# 2high.net
KiCad netlist of a schematic drawn in EAGLE
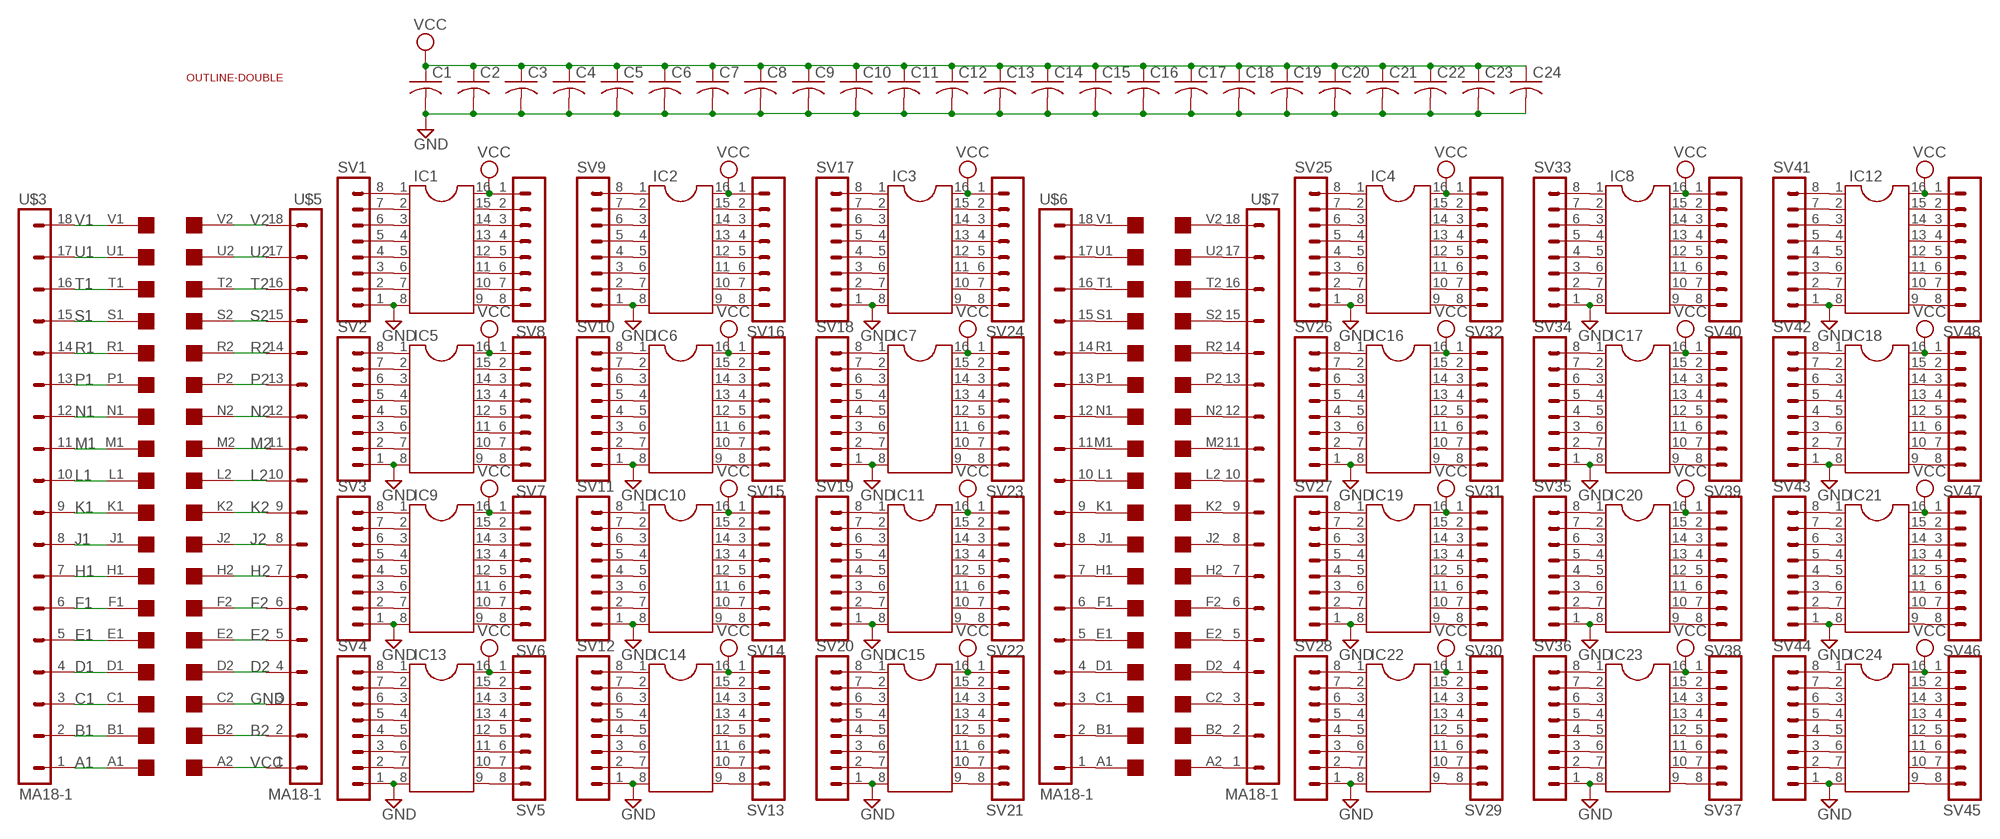
[diagram p0: schematic, sheet 1]

(export (version "E")
  (design (tool "Eeschema 10.0.6"))
  (components
    (comp (ref "C1")
      (value "C-US050-025X075")
      (footprint "eagle-import:C050-025X075")
      (libsource (lib "eagle-import") (part "C-US050-025X075"))
    )
    (comp (ref "C2")
      (value "C-US050-025X075")
      (footprint "eagle-import:C050-025X075")
      (libsource (lib "eagle-import") (part "C-US050-025X075"))
    )
    (comp (ref "C3")
      (value "C-US050-025X075")
      (footprint "eagle-import:C050-025X075")
      (libsource (lib "eagle-import") (part "C-US050-025X075"))
    )
    (comp (ref "C4")
      (value "C-US050-025X075")
      (footprint "eagle-import:C050-025X075")
      (libsource (lib "eagle-import") (part "C-US050-025X075"))
    )
    (comp (ref "C5")
      (value "C-US050-025X075")
      (footprint "eagle-import:C050-025X075")
      (libsource (lib "eagle-import") (part "C-US050-025X075"))
    )
    (comp (ref "C6")
      (value "C-US050-025X075")
      (footprint "eagle-import:C050-025X075")
      (libsource (lib "eagle-import") (part "C-US050-025X075"))
    )
    (comp (ref "C7")
      (value "C-US050-025X075")
      (footprint "eagle-import:C050-025X075")
      (libsource (lib "eagle-import") (part "C-US050-025X075"))
    )
    (comp (ref "C8")
      (value "C-US050-025X075")
      (footprint "eagle-import:C050-025X075")
      (libsource (lib "eagle-import") (part "C-US050-025X075"))
    )
    (comp (ref "C9")
      (value "C-US050-025X075")
      (footprint "eagle-import:C050-025X075")
      (libsource (lib "eagle-import") (part "C-US050-025X075"))
    )
    (comp (ref "C10")
      (value "C-US050-025X075")
      (footprint "eagle-import:C050-025X075")
      (libsource (lib "eagle-import") (part "C-US050-025X075"))
    )
    (comp (ref "C11")
      (value "C-US050-025X075")
      (footprint "eagle-import:C050-025X075")
      (libsource (lib "eagle-import") (part "C-US050-025X075"))
    )
    (comp (ref "C12")
      (value "C-US050-025X075")
      (footprint "eagle-import:C050-025X075")
      (libsource (lib "eagle-import") (part "C-US050-025X075"))
    )
    (comp (ref "C13")
      (value "C-US050-025X075")
      (footprint "eagle-import:C050-025X075")
      (libsource (lib "eagle-import") (part "C-US050-025X075"))
    )
    (comp (ref "C14")
      (value "C-US050-025X075")
      (footprint "eagle-import:C050-025X075")
      (libsource (lib "eagle-import") (part "C-US050-025X075"))
    )
    (comp (ref "C15")
      (value "C-US050-025X075")
      (footprint "eagle-import:C050-025X075")
      (libsource (lib "eagle-import") (part "C-US050-025X075"))
    )
    (comp (ref "C16")
      (value "C-US050-025X075")
      (footprint "eagle-import:C050-025X075")
      (libsource (lib "eagle-import") (part "C-US050-025X075"))
    )
    (comp (ref "C17")
      (value "C-US050-025X075")
      (footprint "eagle-import:C050-025X075")
      (libsource (lib "eagle-import") (part "C-US050-025X075"))
    )
    (comp (ref "C18")
      (value "C-US050-025X075")
      (footprint "eagle-import:C050-025X075")
      (libsource (lib "eagle-import") (part "C-US050-025X075"))
    )
    (comp (ref "C19")
      (value "C-US050-025X075")
      (footprint "eagle-import:C050-025X075")
      (libsource (lib "eagle-import") (part "C-US050-025X075"))
    )
    (comp (ref "C20")
      (value "C-US050-025X075")
      (footprint "eagle-import:C050-025X075")
      (libsource (lib "eagle-import") (part "C-US050-025X075"))
    )
    (comp (ref "C21")
      (value "C-US050-025X075")
      (footprint "eagle-import:C050-025X075")
      (libsource (lib "eagle-import") (part "C-US050-025X075"))
    )
    (comp (ref "C22")
      (value "C-US050-025X075")
      (footprint "eagle-import:C050-025X075")
      (libsource (lib "eagle-import") (part "C-US050-025X075"))
    )
    (comp (ref "C23")
      (value "C-US050-025X075")
      (footprint "eagle-import:C050-025X075")
      (libsource (lib "eagle-import") (part "C-US050-025X075"))
    )
    (comp (ref "C24")
      (value "C-US050-025X075")
      (footprint "eagle-import:C050-025X075")
      (libsource (lib "eagle-import") (part "C-US050-025X075"))
    )
    (comp (ref "IC1")
      (value "DIL16")
      (footprint "eagle-import:DIL16")
      (libsource (lib "eagle-import") (part "DIL16"))
    )
    (comp (ref "IC2")
      (value "DIL16")
      (footprint "eagle-import:DIL16")
      (libsource (lib "eagle-import") (part "DIL16"))
    )
    (comp (ref "IC3")
      (value "DIL16")
      (footprint "eagle-import:DIL16")
      (libsource (lib "eagle-import") (part "DIL16"))
    )
    (comp (ref "IC4")
      (value "DIL16")
      (footprint "eagle-import:DIL16")
      (libsource (lib "eagle-import") (part "DIL16"))
    )
    (comp (ref "IC5")
      (value "DIL16")
      (footprint "eagle-import:DIL16")
      (libsource (lib "eagle-import") (part "DIL16"))
    )
    (comp (ref "IC6")
      (value "DIL16")
      (footprint "eagle-import:DIL16")
      (libsource (lib "eagle-import") (part "DIL16"))
    )
    (comp (ref "IC7")
      (value "DIL16")
      (footprint "eagle-import:DIL16")
      (libsource (lib "eagle-import") (part "DIL16"))
    )
    (comp (ref "IC8")
      (value "DIL16")
      (footprint "eagle-import:DIL16")
      (libsource (lib "eagle-import") (part "DIL16"))
    )
    (comp (ref "IC9")
      (value "DIL16")
      (footprint "eagle-import:DIL16")
      (libsource (lib "eagle-import") (part "DIL16"))
    )
    (comp (ref "IC10")
      (value "DIL16")
      (footprint "eagle-import:DIL16")
      (libsource (lib "eagle-import") (part "DIL16"))
    )
    (comp (ref "IC11")
      (value "DIL16")
      (footprint "eagle-import:DIL16")
      (libsource (lib "eagle-import") (part "DIL16"))
    )
    (comp (ref "IC12")
      (value "DIL16")
      (footprint "eagle-import:DIL16")
      (libsource (lib "eagle-import") (part "DIL16"))
    )
    (comp (ref "IC13")
      (value "DIL16")
      (footprint "eagle-import:DIL16")
      (libsource (lib "eagle-import") (part "DIL16"))
    )
    (comp (ref "IC14")
      (value "DIL16")
      (footprint "eagle-import:DIL16")
      (libsource (lib "eagle-import") (part "DIL16"))
    )
    (comp (ref "IC15")
      (value "DIL16")
      (footprint "eagle-import:DIL16")
      (libsource (lib "eagle-import") (part "DIL16"))
    )
    (comp (ref "IC16")
      (value "DIL16")
      (footprint "eagle-import:DIL16")
      (libsource (lib "eagle-import") (part "DIL16"))
    )
    (comp (ref "IC17")
      (value "DIL16")
      (footprint "eagle-import:DIL16")
      (libsource (lib "eagle-import") (part "DIL16"))
    )
    (comp (ref "IC18")
      (value "DIL16")
      (footprint "eagle-import:DIL16")
      (libsource (lib "eagle-import") (part "DIL16"))
    )
    (comp (ref "IC19")
      (value "DIL16")
      (footprint "eagle-import:DIL16")
      (libsource (lib "eagle-import") (part "DIL16"))
    )
    (comp (ref "IC20")
      (value "DIL16")
      (footprint "eagle-import:DIL16")
      (libsource (lib "eagle-import") (part "DIL16"))
    )
    (comp (ref "IC21")
      (value "DIL16")
      (footprint "eagle-import:DIL16")
      (libsource (lib "eagle-import") (part "DIL16"))
    )
    (comp (ref "IC22")
      (value "DIL16")
      (footprint "eagle-import:DIL16")
      (libsource (lib "eagle-import") (part "DIL16"))
    )
    (comp (ref "IC23")
      (value "DIL16")
      (footprint "eagle-import:DIL16")
      (libsource (lib "eagle-import") (part "DIL16"))
    )
    (comp (ref "IC24")
      (value "DIL16")
      (footprint "eagle-import:DIL16")
      (libsource (lib "eagle-import") (part "DIL16"))
    )
    (comp (ref "SV1")
      (value "MA08-1")
      (footprint "eagle-import:MA08-1")
      (libsource (lib "eagle-import") (part "MA08-1"))
    )
    (comp (ref "SV2")
      (value "MA08-1")
      (footprint "eagle-import:MA08-1")
      (libsource (lib "eagle-import") (part "MA08-1"))
    )
    (comp (ref "SV3")
      (value "MA08-1")
      (footprint "eagle-import:MA08-1")
      (libsource (lib "eagle-import") (part "MA08-1"))
    )
    (comp (ref "SV4")
      (value "MA08-1")
      (footprint "eagle-import:MA08-1")
      (libsource (lib "eagle-import") (part "MA08-1"))
    )
    (comp (ref "SV5")
      (value "MA08-1")
      (footprint "eagle-import:MA08-1")
      (libsource (lib "eagle-import") (part "MA08-1"))
    )
    (comp (ref "SV6")
      (value "MA08-1")
      (footprint "eagle-import:MA08-1")
      (libsource (lib "eagle-import") (part "MA08-1"))
    )
    (comp (ref "SV7")
      (value "MA08-1")
      (footprint "eagle-import:MA08-1")
      (libsource (lib "eagle-import") (part "MA08-1"))
    )
    (comp (ref "SV8")
      (value "MA08-1")
      (footprint "eagle-import:MA08-1")
      (libsource (lib "eagle-import") (part "MA08-1"))
    )
    (comp (ref "SV9")
      (value "MA08-1")
      (footprint "eagle-import:MA08-1")
      (libsource (lib "eagle-import") (part "MA08-1"))
    )
    (comp (ref "SV10")
      (value "MA08-1")
      (footprint "eagle-import:MA08-1")
      (libsource (lib "eagle-import") (part "MA08-1"))
    )
    (comp (ref "SV11")
      (value "MA08-1")
      (footprint "eagle-import:MA08-1")
      (libsource (lib "eagle-import") (part "MA08-1"))
    )
    (comp (ref "SV12")
      (value "MA08-1")
      (footprint "eagle-import:MA08-1")
      (libsource (lib "eagle-import") (part "MA08-1"))
    )
    (comp (ref "SV13")
      (value "MA08-1")
      (footprint "eagle-import:MA08-1")
      (libsource (lib "eagle-import") (part "MA08-1"))
    )
    (comp (ref "SV14")
      (value "MA08-1")
      (footprint "eagle-import:MA08-1")
      (libsource (lib "eagle-import") (part "MA08-1"))
    )
    (comp (ref "SV15")
      (value "MA08-1")
      (footprint "eagle-import:MA08-1")
      (libsource (lib "eagle-import") (part "MA08-1"))
    )
    (comp (ref "SV16")
      (value "MA08-1")
      (footprint "eagle-import:MA08-1")
      (libsource (lib "eagle-import") (part "MA08-1"))
    )
    (comp (ref "SV17")
      (value "MA08-1")
      (footprint "eagle-import:MA08-1")
      (libsource (lib "eagle-import") (part "MA08-1"))
    )
    (comp (ref "SV18")
      (value "MA08-1")
      (footprint "eagle-import:MA08-1")
      (libsource (lib "eagle-import") (part "MA08-1"))
    )
    (comp (ref "SV19")
      (value "MA08-1")
      (footprint "eagle-import:MA08-1")
      (libsource (lib "eagle-import") (part "MA08-1"))
    )
    (comp (ref "SV20")
      (value "MA08-1")
      (footprint "eagle-import:MA08-1")
      (libsource (lib "eagle-import") (part "MA08-1"))
    )
    (comp (ref "SV21")
      (value "MA08-1")
      (footprint "eagle-import:MA08-1")
      (libsource (lib "eagle-import") (part "MA08-1"))
    )
    (comp (ref "SV22")
      (value "MA08-1")
      (footprint "eagle-import:MA08-1")
      (libsource (lib "eagle-import") (part "MA08-1"))
    )
    (comp (ref "SV23")
      (value "MA08-1")
      (footprint "eagle-import:MA08-1")
      (libsource (lib "eagle-import") (part "MA08-1"))
    )
    (comp (ref "SV24")
      (value "MA08-1")
      (footprint "eagle-import:MA08-1")
      (libsource (lib "eagle-import") (part "MA08-1"))
    )
    (comp (ref "SV25")
      (value "MA08-1")
      (footprint "eagle-import:MA08-1")
      (libsource (lib "eagle-import") (part "MA08-1"))
    )
    (comp (ref "SV26")
      (value "MA08-1")
      (footprint "eagle-import:MA08-1")
      (libsource (lib "eagle-import") (part "MA08-1"))
    )
    (comp (ref "SV27")
      (value "MA08-1")
      (footprint "eagle-import:MA08-1")
      (libsource (lib "eagle-import") (part "MA08-1"))
    )
    (comp (ref "SV28")
      (value "MA08-1")
      (footprint "eagle-import:MA08-1")
      (libsource (lib "eagle-import") (part "MA08-1"))
    )
    (comp (ref "SV29")
      (value "MA08-1")
      (footprint "eagle-import:MA08-1")
      (libsource (lib "eagle-import") (part "MA08-1"))
    )
    (comp (ref "SV30")
      (value "MA08-1")
      (footprint "eagle-import:MA08-1")
      (libsource (lib "eagle-import") (part "MA08-1"))
    )
    (comp (ref "SV31")
      (value "MA08-1")
      (footprint "eagle-import:MA08-1")
      (libsource (lib "eagle-import") (part "MA08-1"))
    )
    (comp (ref "SV32")
      (value "MA08-1")
      (footprint "eagle-import:MA08-1")
      (libsource (lib "eagle-import") (part "MA08-1"))
    )
    (comp (ref "SV33")
      (value "MA08-1")
      (footprint "eagle-import:MA08-1")
      (libsource (lib "eagle-import") (part "MA08-1"))
    )
    (comp (ref "SV34")
      (value "MA08-1")
      (footprint "eagle-import:MA08-1")
      (libsource (lib "eagle-import") (part "MA08-1"))
    )
    (comp (ref "SV35")
      (value "MA08-1")
      (footprint "eagle-import:MA08-1")
      (libsource (lib "eagle-import") (part "MA08-1"))
    )
    (comp (ref "SV36")
      (value "MA08-1")
      (footprint "eagle-import:MA08-1")
      (libsource (lib "eagle-import") (part "MA08-1"))
    )
    (comp (ref "SV37")
      (value "MA08-1")
      (footprint "eagle-import:MA08-1")
      (libsource (lib "eagle-import") (part "MA08-1"))
    )
    (comp (ref "SV38")
      (value "MA08-1")
      (footprint "eagle-import:MA08-1")
      (libsource (lib "eagle-import") (part "MA08-1"))
    )
    (comp (ref "SV39")
      (value "MA08-1")
      (footprint "eagle-import:MA08-1")
      (libsource (lib "eagle-import") (part "MA08-1"))
    )
    (comp (ref "SV40")
      (value "MA08-1")
      (footprint "eagle-import:MA08-1")
      (libsource (lib "eagle-import") (part "MA08-1"))
    )
    (comp (ref "SV41")
      (value "MA08-1")
      (footprint "eagle-import:MA08-1")
      (libsource (lib "eagle-import") (part "MA08-1"))
    )
    (comp (ref "SV42")
      (value "MA08-1")
      (footprint "eagle-import:MA08-1")
      (libsource (lib "eagle-import") (part "MA08-1"))
    )
    (comp (ref "SV43")
      (value "MA08-1")
      (footprint "eagle-import:MA08-1")
      (libsource (lib "eagle-import") (part "MA08-1"))
    )
    (comp (ref "SV44")
      (value "MA08-1")
      (footprint "eagle-import:MA08-1")
      (libsource (lib "eagle-import") (part "MA08-1"))
    )
    (comp (ref "SV45")
      (value "MA08-1")
      (footprint "eagle-import:MA08-1")
      (libsource (lib "eagle-import") (part "MA08-1"))
    )
    (comp (ref "SV46")
      (value "MA08-1")
      (footprint "eagle-import:MA08-1")
      (libsource (lib "eagle-import") (part "MA08-1"))
    )
    (comp (ref "SV47")
      (value "MA08-1")
      (footprint "eagle-import:MA08-1")
      (libsource (lib "eagle-import") (part "MA08-1"))
    )
    (comp (ref "SV48")
      (value "MA08-1")
      (footprint "eagle-import:MA08-1")
      (libsource (lib "eagle-import") (part "MA08-1"))
    )
    (comp (ref "U$1")
      (value "OUTLINE-DOUBLE")
      (footprint "eagle-import:DOUBLE")
      (libsource (lib "eagle-import") (part "OUTLINE-DOUBLE"))
    )
    (comp (ref "U$2")
      (value "EDGE-2CONNECTOR")
      (footprint "eagle-import:EDGE-CON2")
      (libsource (lib "eagle-import") (part "EDGE-2CONNECTOR"))
    )
    (comp (ref "U$3")
      (value "MA18-1")
      (footprint "eagle-import:MA18-1")
      (libsource (lib "eagle-import") (part "MA18-1"))
    )
    (comp (ref "U$4")
      (value "EDGE-2CONNECTOR")
      (footprint "eagle-import:EDGE-CON2")
      (libsource (lib "eagle-import") (part "EDGE-2CONNECTOR"))
    )
    (comp (ref "U$5")
      (value "MA18-1")
      (footprint "eagle-import:MA18-1")
      (libsource (lib "eagle-import") (part "MA18-1"))
    )
    (comp (ref "U$6")
      (value "MA18-1")
      (footprint "eagle-import:MA18-1")
      (libsource (lib "eagle-import") (part "MA18-1"))
    )
    (comp (ref "U$7")
      (value "MA18-1")
      (footprint "eagle-import:MA18-1")
      (libsource (lib "eagle-import") (part "MA18-1"))
    )
  )
  (nets
    (net (code "1") (name "/A1") (class "Default")
      (node (ref "U$3") (pin "1") (pinfunction "1_1") (pintype "passive"))
      (node (ref "U$4") (pin "A1") (pinfunction "1_A1") (pintype "bidirectional"))
    )
    (net (code "2") (name "/B1") (class "Default")
      (node (ref "U$3") (pin "2") (pinfunction "2_2") (pintype "passive"))
      (node (ref "U$4") (pin "B1") (pinfunction "1_B1") (pintype "bidirectional"))
    )
    (net (code "3") (name "/B2") (class "Default")
      (node (ref "U$4") (pin "B2") (pinfunction "1_B2") (pintype "bidirectional"))
      (node (ref "U$5") (pin "2") (pinfunction "2_2") (pintype "passive"))
    )
    (net (code "4") (name "/C1") (class "Default")
      (node (ref "U$3") (pin "3") (pinfunction "3_3") (pintype "passive"))
      (node (ref "U$4") (pin "C1") (pinfunction "1_C1") (pintype "bidirectional"))
    )
    (net (code "5") (name "/D1") (class "Default")
      (node (ref "U$3") (pin "4") (pinfunction "4_4") (pintype "passive"))
      (node (ref "U$4") (pin "D1") (pinfunction "1_D1") (pintype "bidirectional"))
    )
    (net (code "6") (name "/D2") (class "Default")
      (node (ref "U$4") (pin "D2") (pinfunction "1_D2") (pintype "bidirectional"))
      (node (ref "U$5") (pin "4") (pinfunction "4_4") (pintype "passive"))
    )
    (net (code "7") (name "/E1") (class "Default")
      (node (ref "U$3") (pin "5") (pinfunction "5_5") (pintype "passive"))
      (node (ref "U$4") (pin "E1") (pinfunction "1_E1") (pintype "bidirectional"))
    )
    (net (code "8") (name "/E2") (class "Default")
      (node (ref "U$4") (pin "E2") (pinfunction "1_E2") (pintype "bidirectional"))
      (node (ref "U$5") (pin "5") (pinfunction "5_5") (pintype "passive"))
    )
    (net (code "9") (name "/F1") (class "Default")
      (node (ref "U$3") (pin "6") (pinfunction "6_6") (pintype "passive"))
      (node (ref "U$4") (pin "F1") (pinfunction "1_F1") (pintype "bidirectional"))
    )
    (net (code "10") (name "/F2") (class "Default")
      (node (ref "U$4") (pin "F2") (pinfunction "1_F2") (pintype "bidirectional"))
      (node (ref "U$5") (pin "6") (pinfunction "6_6") (pintype "passive"))
    )
    (net (code "11") (name "/H1") (class "Default")
      (node (ref "U$3") (pin "7") (pinfunction "7_7") (pintype "passive"))
      (node (ref "U$4") (pin "H1") (pinfunction "1_H1") (pintype "bidirectional"))
    )
    (net (code "12") (name "/H2") (class "Default")
      (node (ref "U$4") (pin "H2") (pinfunction "1_H2") (pintype "bidirectional"))
      (node (ref "U$5") (pin "7") (pinfunction "7_7") (pintype "passive"))
    )
    (net (code "13") (name "/J1") (class "Default")
      (node (ref "U$3") (pin "8") (pinfunction "8_8") (pintype "passive"))
      (node (ref "U$4") (pin "J1") (pinfunction "1_J1") (pintype "bidirectional"))
    )
    (net (code "14") (name "/J2") (class "Default")
      (node (ref "U$4") (pin "J2") (pinfunction "1_J2") (pintype "bidirectional"))
      (node (ref "U$5") (pin "8") (pinfunction "8_8") (pintype "passive"))
    )
    (net (code "15") (name "/K1") (class "Default")
      (node (ref "U$3") (pin "9") (pinfunction "9_9") (pintype "passive"))
      (node (ref "U$4") (pin "K1") (pinfunction "1_K1") (pintype "bidirectional"))
    )
    (net (code "16") (name "/K2") (class "Default")
      (node (ref "U$4") (pin "K2") (pinfunction "1_K2") (pintype "bidirectional"))
      (node (ref "U$5") (pin "9") (pinfunction "9_9") (pintype "passive"))
    )
    (net (code "17") (name "/L1") (class "Default")
      (node (ref "U$3") (pin "10") (pinfunction "10_10") (pintype "passive"))
      (node (ref "U$4") (pin "L1") (pinfunction "1_L1") (pintype "bidirectional"))
    )
    (net (code "18") (name "/L2") (class "Default")
      (node (ref "U$4") (pin "L2") (pinfunction "1_L2") (pintype "bidirectional"))
      (node (ref "U$5") (pin "10") (pinfunction "10_10") (pintype "passive"))
    )
    (net (code "19") (name "/M1") (class "Default")
      (node (ref "U$3") (pin "11") (pinfunction "11_11") (pintype "passive"))
      (node (ref "U$4") (pin "M1") (pinfunction "1_M1") (pintype "bidirectional"))
    )
    (net (code "20") (name "/M2") (class "Default")
      (node (ref "U$4") (pin "M2") (pinfunction "1_M2") (pintype "bidirectional"))
      (node (ref "U$5") (pin "11") (pinfunction "11_11") (pintype "passive"))
    )
    (net (code "21") (name "/N1") (class "Default")
      (node (ref "U$3") (pin "12") (pinfunction "12_12") (pintype "passive"))
      (node (ref "U$4") (pin "N1") (pinfunction "1_N1") (pintype "bidirectional"))
    )
    (net (code "22") (name "/N2") (class "Default")
      (node (ref "U$4") (pin "N2") (pinfunction "1_N2") (pintype "bidirectional"))
      (node (ref "U$5") (pin "12") (pinfunction "12_12") (pintype "passive"))
    )
    (net (code "23") (name "/P1") (class "Default")
      (node (ref "U$3") (pin "13") (pinfunction "13_13") (pintype "passive"))
      (node (ref "U$4") (pin "P1") (pinfunction "1_P1") (pintype "bidirectional"))
    )
    (net (code "24") (name "/P2") (class "Default")
      (node (ref "U$4") (pin "P2") (pinfunction "1_P2") (pintype "bidirectional"))
      (node (ref "U$5") (pin "13") (pinfunction "13_13") (pintype "passive"))
    )
    (net (code "25") (name "/R1") (class "Default")
      (node (ref "U$3") (pin "14") (pinfunction "14_14") (pintype "passive"))
      (node (ref "U$4") (pin "R1") (pinfunction "1_R1") (pintype "bidirectional"))
    )
    (net (code "26") (name "/R2") (class "Default")
      (node (ref "U$4") (pin "R2") (pinfunction "1_R2") (pintype "bidirectional"))
      (node (ref "U$5") (pin "14") (pinfunction "14_14") (pintype "passive"))
    )
    (net (code "27") (name "/S1") (class "Default")
      (node (ref "U$3") (pin "15") (pinfunction "15_15") (pintype "passive"))
      (node (ref "U$4") (pin "S1") (pinfunction "1_S1") (pintype "bidirectional"))
    )
    (net (code "28") (name "/S2") (class "Default")
      (node (ref "U$4") (pin "S2") (pinfunction "1_S2") (pintype "bidirectional"))
      (node (ref "U$5") (pin "15") (pinfunction "15_15") (pintype "passive"))
    )
    (net (code "29") (name "/T1") (class "Default")
      (node (ref "U$3") (pin "16") (pinfunction "16_16") (pintype "passive"))
      (node (ref "U$4") (pin "T1") (pinfunction "1_T1") (pintype "bidirectional"))
    )
    (net (code "30") (name "/T2") (class "Default")
      (node (ref "U$4") (pin "T2") (pinfunction "1_T2") (pintype "bidirectional"))
      (node (ref "U$5") (pin "16") (pinfunction "16_16") (pintype "passive"))
    )
    (net (code "31") (name "/U1") (class "Default")
      (node (ref "U$3") (pin "17") (pinfunction "17_17") (pintype "passive"))
      (node (ref "U$4") (pin "U1") (pinfunction "1_U1") (pintype "bidirectional"))
    )
    (net (code "32") (name "/U2") (class "Default")
      (node (ref "U$4") (pin "U2") (pinfunction "1_U2") (pintype "bidirectional"))
      (node (ref "U$5") (pin "17") (pinfunction "17_17") (pintype "passive"))
    )
    (net (code "33") (name "/V1") (class "Default")
      (node (ref "U$3") (pin "18") (pinfunction "18_18") (pintype "passive"))
      (node (ref "U$4") (pin "V1") (pinfunction "1_V1") (pintype "bidirectional"))
    )
    (net (code "34") (name "/V2") (class "Default")
      (node (ref "U$4") (pin "V2") (pinfunction "1_V2") (pintype "bidirectional"))
      (node (ref "U$5") (pin "18") (pinfunction "18_18") (pintype "passive"))
    )
    (net (code "35") (name "GND") (class "Default")
      (node (ref "C1") (pin "2") (pinfunction "2_2") (pintype "passive"))
      (node (ref "C10") (pin "2") (pinfunction "2_2") (pintype "passive"))
      (node (ref "C11") (pin "2") (pinfunction "2_2") (pintype "passive"))
      (node (ref "C12") (pin "2") (pinfunction "2_2") (pintype "passive"))
      (node (ref "C13") (pin "2") (pinfunction "2_2") (pintype "passive"))
      (node (ref "C14") (pin "2") (pinfunction "2_2") (pintype "passive"))
      (node (ref "C15") (pin "2") (pinfunction "2_2") (pintype "passive"))
      (node (ref "C16") (pin "2") (pinfunction "2_2") (pintype "passive"))
      (node (ref "C17") (pin "2") (pinfunction "2_2") (pintype "passive"))
      (node (ref "C18") (pin "2") (pinfunction "2_2") (pintype "passive"))
      (node (ref "C19") (pin "2") (pinfunction "2_2") (pintype "passive"))
      (node (ref "C2") (pin "2") (pinfunction "2_2") (pintype "passive"))
      (node (ref "C20") (pin "2") (pinfunction "2_2") (pintype "passive"))
      (node (ref "C21") (pin "2") (pinfunction "2_2") (pintype "passive"))
      (node (ref "C22") (pin "2") (pinfunction "2_2") (pintype "passive"))
      (node (ref "C23") (pin "2") (pinfunction "2_2") (pintype "passive"))
      (node (ref "C24") (pin "2") (pinfunction "2_2") (pintype "passive"))
      (node (ref "C3") (pin "2") (pinfunction "2_2") (pintype "passive"))
      (node (ref "C4") (pin "2") (pinfunction "2_2") (pintype "passive"))
      (node (ref "C5") (pin "2") (pinfunction "2_2") (pintype "passive"))
      (node (ref "C6") (pin "2") (pinfunction "2_2") (pintype "passive"))
      (node (ref "C7") (pin "2") (pinfunction "2_2") (pintype "passive"))
      (node (ref "C8") (pin "2") (pinfunction "2_2") (pintype "passive"))
      (node (ref "C9") (pin "2") (pinfunction "2_2") (pintype "passive"))
      (node (ref "IC1") (pin "8") (pinfunction "8_8") (pintype "passive"))
      (node (ref "IC10") (pin "8") (pinfunction "8_8") (pintype "passive"))
      (node (ref "IC11") (pin "8") (pinfunction "8_8") (pintype "passive"))
      (node (ref "IC12") (pin "8") (pinfunction "8_8") (pintype "passive"))
      (node (ref "IC13") (pin "8") (pinfunction "8_8") (pintype "passive"))
      (node (ref "IC14") (pin "8") (pinfunction "8_8") (pintype "passive"))
      (node (ref "IC15") (pin "8") (pinfunction "8_8") (pintype "passive"))
      (node (ref "IC16") (pin "8") (pinfunction "8_8") (pintype "passive"))
      (node (ref "IC17") (pin "8") (pinfunction "8_8") (pintype "passive"))
      (node (ref "IC18") (pin "8") (pinfunction "8_8") (pintype "passive"))
      (node (ref "IC19") (pin "8") (pinfunction "8_8") (pintype "passive"))
      (node (ref "IC2") (pin "8") (pinfunction "8_8") (pintype "passive"))
      (node (ref "IC20") (pin "8") (pinfunction "8_8") (pintype "passive"))
      (node (ref "IC21") (pin "8") (pinfunction "8_8") (pintype "passive"))
      (node (ref "IC22") (pin "8") (pinfunction "8_8") (pintype "passive"))
      (node (ref "IC23") (pin "8") (pinfunction "8_8") (pintype "passive"))
      (node (ref "IC24") (pin "8") (pinfunction "8_8") (pintype "passive"))
      (node (ref "IC3") (pin "8") (pinfunction "8_8") (pintype "passive"))
      (node (ref "IC4") (pin "8") (pinfunction "8_8") (pintype "passive"))
      (node (ref "IC5") (pin "8") (pinfunction "8_8") (pintype "passive"))
      (node (ref "IC6") (pin "8") (pinfunction "8_8") (pintype "passive"))
      (node (ref "IC7") (pin "8") (pinfunction "8_8") (pintype "passive"))
      (node (ref "IC8") (pin "8") (pinfunction "8_8") (pintype "passive"))
      (node (ref "IC9") (pin "8") (pinfunction "8_8") (pintype "passive"))
      (node (ref "SV1") (pin "1") (pinfunction "1_1") (pintype "passive"))
      (node (ref "SV10") (pin "1") (pinfunction "1_1") (pintype "passive"))
      (node (ref "SV11") (pin "1") (pinfunction "1_1") (pintype "passive"))
      (node (ref "SV12") (pin "1") (pinfunction "1_1") (pintype "passive"))
      (node (ref "SV17") (pin "1") (pinfunction "1_1") (pintype "passive"))
      (node (ref "SV18") (pin "1") (pinfunction "1_1") (pintype "passive"))
      (node (ref "SV19") (pin "1") (pinfunction "1_1") (pintype "passive"))
      (node (ref "SV2") (pin "1") (pinfunction "1_1") (pintype "passive"))
      (node (ref "SV20") (pin "1") (pinfunction "1_1") (pintype "passive"))
      (node (ref "SV25") (pin "1") (pinfunction "1_1") (pintype "passive"))
      (node (ref "SV26") (pin "1") (pinfunction "1_1") (pintype "passive"))
      (node (ref "SV27") (pin "1") (pinfunction "1_1") (pintype "passive"))
      (node (ref "SV28") (pin "1") (pinfunction "1_1") (pintype "passive"))
      (node (ref "SV3") (pin "1") (pinfunction "1_1") (pintype "passive"))
      (node (ref "SV33") (pin "1") (pinfunction "1_1") (pintype "passive"))
      (node (ref "SV34") (pin "1") (pinfunction "1_1") (pintype "passive"))
      (node (ref "SV35") (pin "1") (pinfunction "1_1") (pintype "passive"))
      (node (ref "SV36") (pin "1") (pinfunction "1_1") (pintype "passive"))
      (node (ref "SV4") (pin "1") (pinfunction "1_1") (pintype "passive"))
      (node (ref "SV41") (pin "1") (pinfunction "1_1") (pintype "passive"))
      (node (ref "SV42") (pin "1") (pinfunction "1_1") (pintype "passive"))
      (node (ref "SV43") (pin "1") (pinfunction "1_1") (pintype "passive"))
      (node (ref "SV44") (pin "1") (pinfunction "1_1") (pintype "passive"))
      (node (ref "SV9") (pin "1") (pinfunction "1_1") (pintype "passive"))
      (node (ref "U$4") (pin "C2") (pinfunction "1_C2") (pintype "bidirectional"))
      (node (ref "U$5") (pin "3") (pinfunction "3_3") (pintype "passive"))
    )
    (net (code "36") (name "Net-(IC1-Pad1)") (class "Default")
      (node (ref "IC1") (pin "1") (pinfunction "1_1") (pintype "passive"))
      (node (ref "SV1") (pin "8") (pinfunction "8_8") (pintype "passive"))
    )
    (net (code "37") (name "Net-(IC1-Pad2)") (class "Default")
      (node (ref "IC1") (pin "2") (pinfunction "2_2") (pintype "passive"))
      (node (ref "SV1") (pin "7") (pinfunction "7_7") (pintype "passive"))
    )
    (net (code "38") (name "Net-(IC1-Pad3)") (class "Default")
      (node (ref "IC1") (pin "3") (pinfunction "3_3") (pintype "passive"))
      (node (ref "SV1") (pin "6") (pinfunction "6_6") (pintype "passive"))
    )
    (net (code "39") (name "Net-(IC1-Pad4)") (class "Default")
      (node (ref "IC1") (pin "4") (pinfunction "4_4") (pintype "passive"))
      (node (ref "SV1") (pin "5") (pinfunction "5_5") (pintype "passive"))
    )
    (net (code "40") (name "Net-(IC1-Pad5)") (class "Default")
      (node (ref "IC1") (pin "5") (pinfunction "5_5") (pintype "passive"))
      (node (ref "SV1") (pin "4") (pinfunction "4_4") (pintype "passive"))
    )
    (net (code "41") (name "Net-(IC1-Pad6)") (class "Default")
      (node (ref "IC1") (pin "6") (pinfunction "6_6") (pintype "passive"))
      (node (ref "SV1") (pin "3") (pinfunction "3_3") (pintype "passive"))
    )
    (net (code "42") (name "Net-(IC1-Pad7)") (class "Default")
      (node (ref "IC1") (pin "7") (pinfunction "7_7") (pintype "passive"))
      (node (ref "SV1") (pin "2") (pinfunction "2_2") (pintype "passive"))
    )
    (net (code "43") (name "Net-(IC1-Pad9)") (class "Default")
      (node (ref "IC1") (pin "9") (pinfunction "9_9") (pintype "passive"))
      (node (ref "SV8") (pin "8") (pinfunction "8_8") (pintype "passive"))
    )
    (net (code "44") (name "Net-(IC1-Pad10)") (class "Default")
      (node (ref "IC1") (pin "10") (pinfunction "10_10") (pintype "passive"))
      (node (ref "SV8") (pin "7") (pinfunction "7_7") (pintype "passive"))
    )
    (net (code "45") (name "Net-(IC1-Pad11)") (class "Default")
      (node (ref "IC1") (pin "11") (pinfunction "11_11") (pintype "passive"))
      (node (ref "SV8") (pin "6") (pinfunction "6_6") (pintype "passive"))
    )
    (net (code "46") (name "Net-(IC1-Pad12)") (class "Default")
      (node (ref "IC1") (pin "12") (pinfunction "12_12") (pintype "passive"))
      (node (ref "SV8") (pin "5") (pinfunction "5_5") (pintype "passive"))
    )
    (net (code "47") (name "Net-(IC1-Pad13)") (class "Default")
      (node (ref "IC1") (pin "13") (pinfunction "13_13") (pintype "passive"))
      (node (ref "SV8") (pin "4") (pinfunction "4_4") (pintype "passive"))
    )
    (net (code "48") (name "Net-(IC1-Pad14)") (class "Default")
      (node (ref "IC1") (pin "14") (pinfunction "14_14") (pintype "passive"))
      (node (ref "SV8") (pin "3") (pinfunction "3_3") (pintype "passive"))
    )
    (net (code "49") (name "Net-(IC1-Pad15)") (class "Default")
      (node (ref "IC1") (pin "15") (pinfunction "15_15") (pintype "passive"))
      (node (ref "SV8") (pin "2") (pinfunction "2_2") (pintype "passive"))
    )
    (net (code "50") (name "Net-(IC2-Pad1)") (class "Default")
      (node (ref "IC2") (pin "1") (pinfunction "1_1") (pintype "passive"))
      (node (ref "SV9") (pin "8") (pinfunction "8_8") (pintype "passive"))
    )
    (net (code "51") (name "Net-(IC2-Pad2)") (class "Default")
      (node (ref "IC2") (pin "2") (pinfunction "2_2") (pintype "passive"))
      (node (ref "SV9") (pin "7") (pinfunction "7_7") (pintype "passive"))
    )
    (net (code "52") (name "Net-(IC2-Pad3)") (class "Default")
      (node (ref "IC2") (pin "3") (pinfunction "3_3") (pintype "passive"))
      (node (ref "SV9") (pin "6") (pinfunction "6_6") (pintype "passive"))
    )
    (net (code "53") (name "Net-(IC2-Pad4)") (class "Default")
      (node (ref "IC2") (pin "4") (pinfunction "4_4") (pintype "passive"))
      (node (ref "SV9") (pin "5") (pinfunction "5_5") (pintype "passive"))
    )
    (net (code "54") (name "Net-(IC2-Pad5)") (class "Default")
      (node (ref "IC2") (pin "5") (pinfunction "5_5") (pintype "passive"))
      (node (ref "SV9") (pin "4") (pinfunction "4_4") (pintype "passive"))
    )
    (net (code "55") (name "Net-(IC2-Pad6)") (class "Default")
      (node (ref "IC2") (pin "6") (pinfunction "6_6") (pintype "passive"))
      (node (ref "SV9") (pin "3") (pinfunction "3_3") (pintype "passive"))
    )
    (net (code "56") (name "Net-(IC2-Pad7)") (class "Default")
      (node (ref "IC2") (pin "7") (pinfunction "7_7") (pintype "passive"))
      (node (ref "SV9") (pin "2") (pinfunction "2_2") (pintype "passive"))
    )
    (net (code "57") (name "Net-(IC2-Pad9)") (class "Default")
      (node (ref "IC2") (pin "9") (pinfunction "9_9") (pintype "passive"))
      (node (ref "SV16") (pin "8") (pinfunction "8_8") (pintype "passive"))
    )
    (net (code "58") (name "Net-(IC2-Pad10)") (class "Default")
      (node (ref "IC2") (pin "10") (pinfunction "10_10") (pintype "passive"))
      (node (ref "SV16") (pin "7") (pinfunction "7_7") (pintype "passive"))
    )
    (net (code "59") (name "Net-(IC2-Pad11)") (class "Default")
      (node (ref "IC2") (pin "11") (pinfunction "11_11") (pintype "passive"))
      (node (ref "SV16") (pin "6") (pinfunction "6_6") (pintype "passive"))
    )
    (net (code "60") (name "Net-(IC2-Pad12)") (class "Default")
      (node (ref "IC2") (pin "12") (pinfunction "12_12") (pintype "passive"))
      (node (ref "SV16") (pin "5") (pinfunction "5_5") (pintype "passive"))
    )
    (net (code "61") (name "Net-(IC2-Pad13)") (class "Default")
      (node (ref "IC2") (pin "13") (pinfunction "13_13") (pintype "passive"))
      (node (ref "SV16") (pin "4") (pinfunction "4_4") (pintype "passive"))
    )
    (net (code "62") (name "Net-(IC2-Pad14)") (class "Default")
      (node (ref "IC2") (pin "14") (pinfunction "14_14") (pintype "passive"))
      (node (ref "SV16") (pin "3") (pinfunction "3_3") (pintype "passive"))
    )
    (net (code "63") (name "Net-(IC2-Pad15)") (class "Default")
      (node (ref "IC2") (pin "15") (pinfunction "15_15") (pintype "passive"))
      (node (ref "SV16") (pin "2") (pinfunction "2_2") (pintype "passive"))
    )
    (net (code "64") (name "Net-(IC3-Pad1)") (class "Default")
      (node (ref "IC3") (pin "1") (pinfunction "1_1") (pintype "passive"))
      (node (ref "SV17") (pin "8") (pinfunction "8_8") (pintype "passive"))
    )
    (net (code "65") (name "Net-(IC3-Pad2)") (class "Default")
      (node (ref "IC3") (pin "2") (pinfunction "2_2") (pintype "passive"))
      (node (ref "SV17") (pin "7") (pinfunction "7_7") (pintype "passive"))
    )
    (net (code "66") (name "Net-(IC3-Pad3)") (class "Default")
      (node (ref "IC3") (pin "3") (pinfunction "3_3") (pintype "passive"))
      (node (ref "SV17") (pin "6") (pinfunction "6_6") (pintype "passive"))
    )
    (net (code "67") (name "Net-(IC3-Pad4)") (class "Default")
      (node (ref "IC3") (pin "4") (pinfunction "4_4") (pintype "passive"))
      (node (ref "SV17") (pin "5") (pinfunction "5_5") (pintype "passive"))
    )
    (net (code "68") (name "Net-(IC3-Pad5)") (class "Default")
      (node (ref "IC3") (pin "5") (pinfunction "5_5") (pintype "passive"))
      (node (ref "SV17") (pin "4") (pinfunction "4_4") (pintype "passive"))
    )
    (net (code "69") (name "Net-(IC3-Pad6)") (class "Default")
      (node (ref "IC3") (pin "6") (pinfunction "6_6") (pintype "passive"))
      (node (ref "SV17") (pin "3") (pinfunction "3_3") (pintype "passive"))
    )
    (net (code "70") (name "Net-(IC3-Pad7)") (class "Default")
      (node (ref "IC3") (pin "7") (pinfunction "7_7") (pintype "passive"))
      (node (ref "SV17") (pin "2") (pinfunction "2_2") (pintype "passive"))
    )
    (net (code "71") (name "Net-(IC3-Pad9)") (class "Default")
      (node (ref "IC3") (pin "9") (pinfunction "9_9") (pintype "passive"))
      (node (ref "SV24") (pin "8") (pinfunction "8_8") (pintype "passive"))
    )
    (net (code "72") (name "Net-(IC3-Pad10)") (class "Default")
      (node (ref "IC3") (pin "10") (pinfunction "10_10") (pintype "passive"))
      (node (ref "SV24") (pin "7") (pinfunction "7_7") (pintype "passive"))
    )
    (net (code "73") (name "Net-(IC3-Pad11)") (class "Default")
      (node (ref "IC3") (pin "11") (pinfunction "11_11") (pintype "passive"))
      (node (ref "SV24") (pin "6") (pinfunction "6_6") (pintype "passive"))
    )
    (net (code "74") (name "Net-(IC3-Pad12)") (class "Default")
      (node (ref "IC3") (pin "12") (pinfunction "12_12") (pintype "passive"))
      (node (ref "SV24") (pin "5") (pinfunction "5_5") (pintype "passive"))
    )
    (net (code "75") (name "Net-(IC3-Pad13)") (class "Default")
      (node (ref "IC3") (pin "13") (pinfunction "13_13") (pintype "passive"))
      (node (ref "SV24") (pin "4") (pinfunction "4_4") (pintype "passive"))
    )
    (net (code "76") (name "Net-(IC3-Pad14)") (class "Default")
      (node (ref "IC3") (pin "14") (pinfunction "14_14") (pintype "passive"))
      (node (ref "SV24") (pin "3") (pinfunction "3_3") (pintype "passive"))
    )
    (net (code "77") (name "Net-(IC3-Pad15)") (class "Default")
      (node (ref "IC3") (pin "15") (pinfunction "15_15") (pintype "passive"))
      (node (ref "SV24") (pin "2") (pinfunction "2_2") (pintype "passive"))
    )
    (net (code "78") (name "Net-(IC4-Pad1)") (class "Default")
      (node (ref "IC4") (pin "1") (pinfunction "1_1") (pintype "passive"))
      (node (ref "SV25") (pin "8") (pinfunction "8_8") (pintype "passive"))
    )
    (net (code "79") (name "Net-(IC4-Pad2)") (class "Default")
      (node (ref "IC4") (pin "2") (pinfunction "2_2") (pintype "passive"))
      (node (ref "SV25") (pin "7") (pinfunction "7_7") (pintype "passive"))
    )
    (net (code "80") (name "Net-(IC4-Pad3)") (class "Default")
      (node (ref "IC4") (pin "3") (pinfunction "3_3") (pintype "passive"))
      (node (ref "SV25") (pin "6") (pinfunction "6_6") (pintype "passive"))
    )
    (net (code "81") (name "Net-(IC4-Pad4)") (class "Default")
      (node (ref "IC4") (pin "4") (pinfunction "4_4") (pintype "passive"))
      (node (ref "SV25") (pin "5") (pinfunction "5_5") (pintype "passive"))
    )
    (net (code "82") (name "Net-(IC4-Pad5)") (class "Default")
      (node (ref "IC4") (pin "5") (pinfunction "5_5") (pintype "passive"))
      (node (ref "SV25") (pin "4") (pinfunction "4_4") (pintype "passive"))
    )
    (net (code "83") (name "Net-(IC4-Pad6)") (class "Default")
      (node (ref "IC4") (pin "6") (pinfunction "6_6") (pintype "passive"))
      (node (ref "SV25") (pin "3") (pinfunction "3_3") (pintype "passive"))
    )
    (net (code "84") (name "Net-(IC4-Pad7)") (class "Default")
      (node (ref "IC4") (pin "7") (pinfunction "7_7") (pintype "passive"))
      (node (ref "SV25") (pin "2") (pinfunction "2_2") (pintype "passive"))
    )
    (net (code "85") (name "Net-(IC4-Pad9)") (class "Default")
      (node (ref "IC4") (pin "9") (pinfunction "9_9") (pintype "passive"))
      (node (ref "SV32") (pin "8") (pinfunction "8_8") (pintype "passive"))
    )
    (net (code "86") (name "Net-(IC4-Pad10)") (class "Default")
      (node (ref "IC4") (pin "10") (pinfunction "10_10") (pintype "passive"))
      (node (ref "SV32") (pin "7") (pinfunction "7_7") (pintype "passive"))
    )
    (net (code "87") (name "Net-(IC4-Pad11)") (class "Default")
      (node (ref "IC4") (pin "11") (pinfunction "11_11") (pintype "passive"))
      (node (ref "SV32") (pin "6") (pinfunction "6_6") (pintype "passive"))
    )
    (net (code "88") (name "Net-(IC4-Pad12)") (class "Default")
      (node (ref "IC4") (pin "12") (pinfunction "12_12") (pintype "passive"))
      (node (ref "SV32") (pin "5") (pinfunction "5_5") (pintype "passive"))
    )
    (net (code "89") (name "Net-(IC4-Pad13)") (class "Default")
      (node (ref "IC4") (pin "13") (pinfunction "13_13") (pintype "passive"))
      (node (ref "SV32") (pin "4") (pinfunction "4_4") (pintype "passive"))
    )
    (net (code "90") (name "Net-(IC4-Pad14)") (class "Default")
      (node (ref "IC4") (pin "14") (pinfunction "14_14") (pintype "passive"))
      (node (ref "SV32") (pin "3") (pinfunction "3_3") (pintype "passive"))
    )
    (net (code "91") (name "Net-(IC4-Pad15)") (class "Default")
      (node (ref "IC4") (pin "15") (pinfunction "15_15") (pintype "passive"))
      (node (ref "SV32") (pin "2") (pinfunction "2_2") (pintype "passive"))
    )
    (net (code "92") (name "Net-(IC5-Pad1)") (class "Default")
      (node (ref "IC5") (pin "1") (pinfunction "1_1") (pintype "passive"))
      (node (ref "SV2") (pin "8") (pinfunction "8_8") (pintype "passive"))
    )
    (net (code "93") (name "Net-(IC5-Pad2)") (class "Default")
      (node (ref "IC5") (pin "2") (pinfunction "2_2") (pintype "passive"))
      (node (ref "SV2") (pin "7") (pinfunction "7_7") (pintype "passive"))
    )
    (net (code "94") (name "Net-(IC5-Pad3)") (class "Default")
      (node (ref "IC5") (pin "3") (pinfunction "3_3") (pintype "passive"))
      (node (ref "SV2") (pin "6") (pinfunction "6_6") (pintype "passive"))
    )
    (net (code "95") (name "Net-(IC5-Pad4)") (class "Default")
      (node (ref "IC5") (pin "4") (pinfunction "4_4") (pintype "passive"))
      (node (ref "SV2") (pin "5") (pinfunction "5_5") (pintype "passive"))
    )
    (net (code "96") (name "Net-(IC5-Pad5)") (class "Default")
      (node (ref "IC5") (pin "5") (pinfunction "5_5") (pintype "passive"))
      (node (ref "SV2") (pin "4") (pinfunction "4_4") (pintype "passive"))
    )
    (net (code "97") (name "Net-(IC5-Pad6)") (class "Default")
      (node (ref "IC5") (pin "6") (pinfunction "6_6") (pintype "passive"))
      (node (ref "SV2") (pin "3") (pinfunction "3_3") (pintype "passive"))
    )
    (net (code "98") (name "Net-(IC5-Pad7)") (class "Default")
      (node (ref "IC5") (pin "7") (pinfunction "7_7") (pintype "passive"))
      (node (ref "SV2") (pin "2") (pinfunction "2_2") (pintype "passive"))
    )
    (net (code "99") (name "Net-(IC5-Pad9)") (class "Default")
      (node (ref "IC5") (pin "9") (pinfunction "9_9") (pintype "passive"))
      (node (ref "SV7") (pin "8") (pinfunction "8_8") (pintype "passive"))
    )
    (net (code "100") (name "Net-(IC5-Pad10)") (class "Default")
      (node (ref "IC5") (pin "10") (pinfunction "10_10") (pintype "passive"))
      (node (ref "SV7") (pin "7") (pinfunction "7_7") (pintype "passive"))
    )
    (net (code "101") (name "Net-(IC5-Pad11)") (class "Default")
      (node (ref "IC5") (pin "11") (pinfunction "11_11") (pintype "passive"))
      (node (ref "SV7") (pin "6") (pinfunction "6_6") (pintype "passive"))
    )
    (net (code "102") (name "Net-(IC5-Pad12)") (class "Default")
      (node (ref "IC5") (pin "12") (pinfunction "12_12") (pintype "passive"))
      (node (ref "SV7") (pin "5") (pinfunction "5_5") (pintype "passive"))
    )
    (net (code "103") (name "Net-(IC5-Pad13)") (class "Default")
      (node (ref "IC5") (pin "13") (pinfunction "13_13") (pintype "passive"))
      (node (ref "SV7") (pin "4") (pinfunction "4_4") (pintype "passive"))
    )
    (net (code "104") (name "Net-(IC5-Pad14)") (class "Default")
      (node (ref "IC5") (pin "14") (pinfunction "14_14") (pintype "passive"))
      (node (ref "SV7") (pin "3") (pinfunction "3_3") (pintype "passive"))
    )
    (net (code "105") (name "Net-(IC5-Pad15)") (class "Default")
      (node (ref "IC5") (pin "15") (pinfunction "15_15") (pintype "passive"))
      (node (ref "SV7") (pin "2") (pinfunction "2_2") (pintype "passive"))
    )
    (net (code "106") (name "Net-(IC6-Pad1)") (class "Default")
      (node (ref "IC6") (pin "1") (pinfunction "1_1") (pintype "passive"))
      (node (ref "SV10") (pin "8") (pinfunction "8_8") (pintype "passive"))
    )
    (net (code "107") (name "Net-(IC6-Pad2)") (class "Default")
      (node (ref "IC6") (pin "2") (pinfunction "2_2") (pintype "passive"))
      (node (ref "SV10") (pin "7") (pinfunction "7_7") (pintype "passive"))
    )
    (net (code "108") (name "Net-(IC6-Pad3)") (class "Default")
      (node (ref "IC6") (pin "3") (pinfunction "3_3") (pintype "passive"))
      (node (ref "SV10") (pin "6") (pinfunction "6_6") (pintype "passive"))
    )
    (net (code "109") (name "Net-(IC6-Pad4)") (class "Default")
      (node (ref "IC6") (pin "4") (pinfunction "4_4") (pintype "passive"))
      (node (ref "SV10") (pin "5") (pinfunction "5_5") (pintype "passive"))
    )
    (net (code "110") (name "Net-(IC6-Pad5)") (class "Default")
      (node (ref "IC6") (pin "5") (pinfunction "5_5") (pintype "passive"))
      (node (ref "SV10") (pin "4") (pinfunction "4_4") (pintype "passive"))
    )
    (net (code "111") (name "Net-(IC6-Pad6)") (class "Default")
      (node (ref "IC6") (pin "6") (pinfunction "6_6") (pintype "passive"))
      (node (ref "SV10") (pin "3") (pinfunction "3_3") (pintype "passive"))
    )
    (net (code "112") (name "Net-(IC6-Pad7)") (class "Default")
      (node (ref "IC6") (pin "7") (pinfunction "7_7") (pintype "passive"))
      (node (ref "SV10") (pin "2") (pinfunction "2_2") (pintype "passive"))
    )
    (net (code "113") (name "Net-(IC6-Pad9)") (class "Default")
      (node (ref "IC6") (pin "9") (pinfunction "9_9") (pintype "passive"))
      (node (ref "SV15") (pin "8") (pinfunction "8_8") (pintype "passive"))
    )
    (net (code "114") (name "Net-(IC6-Pad10)") (class "Default")
      (node (ref "IC6") (pin "10") (pinfunction "10_10") (pintype "passive"))
      (node (ref "SV15") (pin "7") (pinfunction "7_7") (pintype "passive"))
    )
    (net (code "115") (name "Net-(IC6-Pad11)") (class "Default")
      (node (ref "IC6") (pin "11") (pinfunction "11_11") (pintype "passive"))
      (node (ref "SV15") (pin "6") (pinfunction "6_6") (pintype "passive"))
    )
    (net (code "116") (name "Net-(IC6-Pad12)") (class "Default")
      (node (ref "IC6") (pin "12") (pinfunction "12_12") (pintype "passive"))
      (node (ref "SV15") (pin "5") (pinfunction "5_5") (pintype "passive"))
    )
    (net (code "117") (name "Net-(IC6-Pad13)") (class "Default")
      (node (ref "IC6") (pin "13") (pinfunction "13_13") (pintype "passive"))
      (node (ref "SV15") (pin "4") (pinfunction "4_4") (pintype "passive"))
    )
    (net (code "118") (name "Net-(IC6-Pad14)") (class "Default")
      (node (ref "IC6") (pin "14") (pinfunction "14_14") (pintype "passive"))
      (node (ref "SV15") (pin "3") (pinfunction "3_3") (pintype "passive"))
    )
    (net (code "119") (name "Net-(IC6-Pad15)") (class "Default")
      (node (ref "IC6") (pin "15") (pinfunction "15_15") (pintype "passive"))
      (node (ref "SV15") (pin "2") (pinfunction "2_2") (pintype "passive"))
    )
    (net (code "120") (name "Net-(IC7-Pad1)") (class "Default")
      (node (ref "IC7") (pin "1") (pinfunction "1_1") (pintype "passive"))
      (node (ref "SV18") (pin "8") (pinfunction "8_8") (pintype "passive"))
    )
    (net (code "121") (name "Net-(IC7-Pad2)") (class "Default")
      (node (ref "IC7") (pin "2") (pinfunction "2_2") (pintype "passive"))
      (node (ref "SV18") (pin "7") (pinfunction "7_7") (pintype "passive"))
    )
    (net (code "122") (name "Net-(IC7-Pad3)") (class "Default")
      (node (ref "IC7") (pin "3") (pinfunction "3_3") (pintype "passive"))
      (node (ref "SV18") (pin "6") (pinfunction "6_6") (pintype "passive"))
    )
    (net (code "123") (name "Net-(IC7-Pad4)") (class "Default")
      (node (ref "IC7") (pin "4") (pinfunction "4_4") (pintype "passive"))
      (node (ref "SV18") (pin "5") (pinfunction "5_5") (pintype "passive"))
    )
    (net (code "124") (name "Net-(IC7-Pad5)") (class "Default")
      (node (ref "IC7") (pin "5") (pinfunction "5_5") (pintype "passive"))
      (node (ref "SV18") (pin "4") (pinfunction "4_4") (pintype "passive"))
    )
    (net (code "125") (name "Net-(IC7-Pad6)") (class "Default")
      (node (ref "IC7") (pin "6") (pinfunction "6_6") (pintype "passive"))
      (node (ref "SV18") (pin "3") (pinfunction "3_3") (pintype "passive"))
    )
    (net (code "126") (name "Net-(IC7-Pad7)") (class "Default")
      (node (ref "IC7") (pin "7") (pinfunction "7_7") (pintype "passive"))
      (node (ref "SV18") (pin "2") (pinfunction "2_2") (pintype "passive"))
    )
    (net (code "127") (name "Net-(IC7-Pad9)") (class "Default")
      (node (ref "IC7") (pin "9") (pinfunction "9_9") (pintype "passive"))
      (node (ref "SV23") (pin "8") (pinfunction "8_8") (pintype "passive"))
    )
    (net (code "128") (name "Net-(IC7-Pad10)") (class "Default")
      (node (ref "IC7") (pin "10") (pinfunction "10_10") (pintype "passive"))
      (node (ref "SV23") (pin "7") (pinfunction "7_7") (pintype "passive"))
    )
    (net (code "129") (name "Net-(IC7-Pad11)") (class "Default")
      (node (ref "IC7") (pin "11") (pinfunction "11_11") (pintype "passive"))
      (node (ref "SV23") (pin "6") (pinfunction "6_6") (pintype "passive"))
    )
    (net (code "130") (name "Net-(IC7-Pad12)") (class "Default")
      (node (ref "IC7") (pin "12") (pinfunction "12_12") (pintype "passive"))
      (node (ref "SV23") (pin "5") (pinfunction "5_5") (pintype "passive"))
    )
    (net (code "131") (name "Net-(IC7-Pad13)") (class "Default")
      (node (ref "IC7") (pin "13") (pinfunction "13_13") (pintype "passive"))
      (node (ref "SV23") (pin "4") (pinfunction "4_4") (pintype "passive"))
    )
    (net (code "132") (name "Net-(IC7-Pad14)") (class "Default")
      (node (ref "IC7") (pin "14") (pinfunction "14_14") (pintype "passive"))
      (node (ref "SV23") (pin "3") (pinfunction "3_3") (pintype "passive"))
    )
    (net (code "133") (name "Net-(IC7-Pad15)") (class "Default")
      (node (ref "IC7") (pin "15") (pinfunction "15_15") (pintype "passive"))
      (node (ref "SV23") (pin "2") (pinfunction "2_2") (pintype "passive"))
    )
    (net (code "134") (name "Net-(IC8-Pad1)") (class "Default")
      (node (ref "IC8") (pin "1") (pinfunction "1_1") (pintype "passive"))
      (node (ref "SV33") (pin "8") (pinfunction "8_8") (pintype "passive"))
    )
    (net (code "135") (name "Net-(IC8-Pad2)") (class "Default")
      (node (ref "IC8") (pin "2") (pinfunction "2_2") (pintype "passive"))
      (node (ref "SV33") (pin "7") (pinfunction "7_7") (pintype "passive"))
    )
    (net (code "136") (name "Net-(IC8-Pad3)") (class "Default")
      (node (ref "IC8") (pin "3") (pinfunction "3_3") (pintype "passive"))
      (node (ref "SV33") (pin "6") (pinfunction "6_6") (pintype "passive"))
    )
    (net (code "137") (name "Net-(IC8-Pad4)") (class "Default")
      (node (ref "IC8") (pin "4") (pinfunction "4_4") (pintype "passive"))
      (node (ref "SV33") (pin "5") (pinfunction "5_5") (pintype "passive"))
    )
    (net (code "138") (name "Net-(IC8-Pad5)") (class "Default")
      (node (ref "IC8") (pin "5") (pinfunction "5_5") (pintype "passive"))
      (node (ref "SV33") (pin "4") (pinfunction "4_4") (pintype "passive"))
    )
    (net (code "139") (name "Net-(IC8-Pad6)") (class "Default")
      (node (ref "IC8") (pin "6") (pinfunction "6_6") (pintype "passive"))
      (node (ref "SV33") (pin "3") (pinfunction "3_3") (pintype "passive"))
    )
    (net (code "140") (name "Net-(IC8-Pad7)") (class "Default")
      (node (ref "IC8") (pin "7") (pinfunction "7_7") (pintype "passive"))
      (node (ref "SV33") (pin "2") (pinfunction "2_2") (pintype "passive"))
    )
    (net (code "141") (name "Net-(IC8-Pad9)") (class "Default")
      (node (ref "IC8") (pin "9") (pinfunction "9_9") (pintype "passive"))
      (node (ref "SV40") (pin "8") (pinfunction "8_8") (pintype "passive"))
    )
    (net (code "142") (name "Net-(IC8-Pad10)") (class "Default")
      (node (ref "IC8") (pin "10") (pinfunction "10_10") (pintype "passive"))
      (node (ref "SV40") (pin "7") (pinfunction "7_7") (pintype "passive"))
    )
    (net (code "143") (name "Net-(IC8-Pad11)") (class "Default")
      (node (ref "IC8") (pin "11") (pinfunction "11_11") (pintype "passive"))
      (node (ref "SV40") (pin "6") (pinfunction "6_6") (pintype "passive"))
    )
    (net (code "144") (name "Net-(IC8-Pad12)") (class "Default")
      (node (ref "IC8") (pin "12") (pinfunction "12_12") (pintype "passive"))
      (node (ref "SV40") (pin "5") (pinfunction "5_5") (pintype "passive"))
    )
    (net (code "145") (name "Net-(IC8-Pad13)") (class "Default")
      (node (ref "IC8") (pin "13") (pinfunction "13_13") (pintype "passive"))
      (node (ref "SV40") (pin "4") (pinfunction "4_4") (pintype "passive"))
    )
    (net (code "146") (name "Net-(IC8-Pad14)") (class "Default")
      (node (ref "IC8") (pin "14") (pinfunction "14_14") (pintype "passive"))
      (node (ref "SV40") (pin "3") (pinfunction "3_3") (pintype "passive"))
    )
    (net (code "147") (name "Net-(IC8-Pad15)") (class "Default")
      (node (ref "IC8") (pin "15") (pinfunction "15_15") (pintype "passive"))
      (node (ref "SV40") (pin "2") (pinfunction "2_2") (pintype "passive"))
    )
    (net (code "148") (name "Net-(IC9-Pad1)") (class "Default")
      (node (ref "IC9") (pin "1") (pinfunction "1_1") (pintype "passive"))
      (node (ref "SV3") (pin "8") (pinfunction "8_8") (pintype "passive"))
    )
    (net (code "149") (name "Net-(IC9-Pad2)") (class "Default")
      (node (ref "IC9") (pin "2") (pinfunction "2_2") (pintype "passive"))
      (node (ref "SV3") (pin "7") (pinfunction "7_7") (pintype "passive"))
    )
    (net (code "150") (name "Net-(IC9-Pad3)") (class "Default")
      (node (ref "IC9") (pin "3") (pinfunction "3_3") (pintype "passive"))
      (node (ref "SV3") (pin "6") (pinfunction "6_6") (pintype "passive"))
    )
    (net (code "151") (name "Net-(IC9-Pad4)") (class "Default")
      (node (ref "IC9") (pin "4") (pinfunction "4_4") (pintype "passive"))
      (node (ref "SV3") (pin "5") (pinfunction "5_5") (pintype "passive"))
    )
    (net (code "152") (name "Net-(IC9-Pad5)") (class "Default")
      (node (ref "IC9") (pin "5") (pinfunction "5_5") (pintype "passive"))
      (node (ref "SV3") (pin "4") (pinfunction "4_4") (pintype "passive"))
    )
    (net (code "153") (name "Net-(IC9-Pad6)") (class "Default")
      (node (ref "IC9") (pin "6") (pinfunction "6_6") (pintype "passive"))
      (node (ref "SV3") (pin "3") (pinfunction "3_3") (pintype "passive"))
    )
    (net (code "154") (name "Net-(IC9-Pad7)") (class "Default")
      (node (ref "IC9") (pin "7") (pinfunction "7_7") (pintype "passive"))
      (node (ref "SV3") (pin "2") (pinfunction "2_2") (pintype "passive"))
    )
    (net (code "155") (name "Net-(IC9-Pad9)") (class "Default")
      (node (ref "IC9") (pin "9") (pinfunction "9_9") (pintype "passive"))
      (node (ref "SV6") (pin "8") (pinfunction "8_8") (pintype "passive"))
    )
    (net (code "156") (name "Net-(IC9-Pad10)") (class "Default")
      (node (ref "IC9") (pin "10") (pinfunction "10_10") (pintype "passive"))
      (node (ref "SV6") (pin "7") (pinfunction "7_7") (pintype "passive"))
    )
    (net (code "157") (name "Net-(IC9-Pad11)") (class "Default")
      (node (ref "IC9") (pin "11") (pinfunction "11_11") (pintype "passive"))
      (node (ref "SV6") (pin "6") (pinfunction "6_6") (pintype "passive"))
    )
    (net (code "158") (name "Net-(IC9-Pad12)") (class "Default")
      (node (ref "IC9") (pin "12") (pinfunction "12_12") (pintype "passive"))
      (node (ref "SV6") (pin "5") (pinfunction "5_5") (pintype "passive"))
    )
    (net (code "159") (name "Net-(IC9-Pad13)") (class "Default")
      (node (ref "IC9") (pin "13") (pinfunction "13_13") (pintype "passive"))
      (node (ref "SV6") (pin "4") (pinfunction "4_4") (pintype "passive"))
    )
    (net (code "160") (name "Net-(IC9-Pad14)") (class "Default")
      (node (ref "IC9") (pin "14") (pinfunction "14_14") (pintype "passive"))
      (node (ref "SV6") (pin "3") (pinfunction "3_3") (pintype "passive"))
    )
    (net (code "161") (name "Net-(IC9-Pad15)") (class "Default")
      (node (ref "IC9") (pin "15") (pinfunction "15_15") (pintype "passive"))
      (node (ref "SV6") (pin "2") (pinfunction "2_2") (pintype "passive"))
    )
    (net (code "162") (name "Net-(IC10-Pad1)") (class "Default")
      (node (ref "IC10") (pin "1") (pinfunction "1_1") (pintype "passive"))
      (node (ref "SV11") (pin "8") (pinfunction "8_8") (pintype "passive"))
    )
    (net (code "163") (name "Net-(IC10-Pad2)") (class "Default")
      (node (ref "IC10") (pin "2") (pinfunction "2_2") (pintype "passive"))
      (node (ref "SV11") (pin "7") (pinfunction "7_7") (pintype "passive"))
    )
    (net (code "164") (name "Net-(IC10-Pad3)") (class "Default")
      (node (ref "IC10") (pin "3") (pinfunction "3_3") (pintype "passive"))
      (node (ref "SV11") (pin "6") (pinfunction "6_6") (pintype "passive"))
    )
    (net (code "165") (name "Net-(IC10-Pad4)") (class "Default")
      (node (ref "IC10") (pin "4") (pinfunction "4_4") (pintype "passive"))
      (node (ref "SV11") (pin "5") (pinfunction "5_5") (pintype "passive"))
    )
    (net (code "166") (name "Net-(IC10-Pad5)") (class "Default")
      (node (ref "IC10") (pin "5") (pinfunction "5_5") (pintype "passive"))
      (node (ref "SV11") (pin "4") (pinfunction "4_4") (pintype "passive"))
    )
    (net (code "167") (name "Net-(IC10-Pad6)") (class "Default")
      (node (ref "IC10") (pin "6") (pinfunction "6_6") (pintype "passive"))
      (node (ref "SV11") (pin "3") (pinfunction "3_3") (pintype "passive"))
    )
    (net (code "168") (name "Net-(IC10-Pad7)") (class "Default")
      (node (ref "IC10") (pin "7") (pinfunction "7_7") (pintype "passive"))
      (node (ref "SV11") (pin "2") (pinfunction "2_2") (pintype "passive"))
    )
    (net (code "169") (name "Net-(IC10-Pad9)") (class "Default")
      (node (ref "IC10") (pin "9") (pinfunction "9_9") (pintype "passive"))
      (node (ref "SV14") (pin "8") (pinfunction "8_8") (pintype "passive"))
    )
    (net (code "170") (name "Net-(IC10-Pad10)") (class "Default")
      (node (ref "IC10") (pin "10") (pinfunction "10_10") (pintype "passive"))
      (node (ref "SV14") (pin "7") (pinfunction "7_7") (pintype "passive"))
    )
    (net (code "171") (name "Net-(IC10-Pad11)") (class "Default")
      (node (ref "IC10") (pin "11") (pinfunction "11_11") (pintype "passive"))
      (node (ref "SV14") (pin "6") (pinfunction "6_6") (pintype "passive"))
    )
    (net (code "172") (name "Net-(IC10-Pad12)") (class "Default")
      (node (ref "IC10") (pin "12") (pinfunction "12_12") (pintype "passive"))
      (node (ref "SV14") (pin "5") (pinfunction "5_5") (pintype "passive"))
    )
    (net (code "173") (name "Net-(IC10-Pad13)") (class "Default")
      (node (ref "IC10") (pin "13") (pinfunction "13_13") (pintype "passive"))
      (node (ref "SV14") (pin "4") (pinfunction "4_4") (pintype "passive"))
    )
    (net (code "174") (name "Net-(IC10-Pad14)") (class "Default")
      (node (ref "IC10") (pin "14") (pinfunction "14_14") (pintype "passive"))
      (node (ref "SV14") (pin "3") (pinfunction "3_3") (pintype "passive"))
    )
    (net (code "175") (name "Net-(IC10-Pad15)") (class "Default")
      (node (ref "IC10") (pin "15") (pinfunction "15_15") (pintype "passive"))
      (node (ref "SV14") (pin "2") (pinfunction "2_2") (pintype "passive"))
    )
    (net (code "176") (name "Net-(IC11-Pad1)") (class "Default")
      (node (ref "IC11") (pin "1") (pinfunction "1_1") (pintype "passive"))
      (node (ref "SV19") (pin "8") (pinfunction "8_8") (pintype "passive"))
    )
    (net (code "177") (name "Net-(IC11-Pad2)") (class "Default")
      (node (ref "IC11") (pin "2") (pinfunction "2_2") (pintype "passive"))
      (node (ref "SV19") (pin "7") (pinfunction "7_7") (pintype "passive"))
    )
    (net (code "178") (name "Net-(IC11-Pad3)") (class "Default")
      (node (ref "IC11") (pin "3") (pinfunction "3_3") (pintype "passive"))
      (node (ref "SV19") (pin "6") (pinfunction "6_6") (pintype "passive"))
    )
    (net (code "179") (name "Net-(IC11-Pad4)") (class "Default")
      (node (ref "IC11") (pin "4") (pinfunction "4_4") (pintype "passive"))
      (node (ref "SV19") (pin "5") (pinfunction "5_5") (pintype "passive"))
    )
    (net (code "180") (name "Net-(IC11-Pad5)") (class "Default")
      (node (ref "IC11") (pin "5") (pinfunction "5_5") (pintype "passive"))
      (node (ref "SV19") (pin "4") (pinfunction "4_4") (pintype "passive"))
    )
    (net (code "181") (name "Net-(IC11-Pad6)") (class "Default")
      (node (ref "IC11") (pin "6") (pinfunction "6_6") (pintype "passive"))
      (node (ref "SV19") (pin "3") (pinfunction "3_3") (pintype "passive"))
    )
    (net (code "182") (name "Net-(IC11-Pad7)") (class "Default")
      (node (ref "IC11") (pin "7") (pinfunction "7_7") (pintype "passive"))
      (node (ref "SV19") (pin "2") (pinfunction "2_2") (pintype "passive"))
    )
    (net (code "183") (name "Net-(IC11-Pad9)") (class "Default")
      (node (ref "IC11") (pin "9") (pinfunction "9_9") (pintype "passive"))
      (node (ref "SV22") (pin "8") (pinfunction "8_8") (pintype "passive"))
    )
    (net (code "184") (name "Net-(IC11-Pad10)") (class "Default")
      (node (ref "IC11") (pin "10") (pinfunction "10_10") (pintype "passive"))
      (node (ref "SV22") (pin "7") (pinfunction "7_7") (pintype "passive"))
    )
    (net (code "185") (name "Net-(IC11-Pad11)") (class "Default")
      (node (ref "IC11") (pin "11") (pinfunction "11_11") (pintype "passive"))
      (node (ref "SV22") (pin "6") (pinfunction "6_6") (pintype "passive"))
    )
    (net (code "186") (name "Net-(IC11-Pad12)") (class "Default")
      (node (ref "IC11") (pin "12") (pinfunction "12_12") (pintype "passive"))
      (node (ref "SV22") (pin "5") (pinfunction "5_5") (pintype "passive"))
    )
    (net (code "187") (name "Net-(IC11-Pad13)") (class "Default")
      (node (ref "IC11") (pin "13") (pinfunction "13_13") (pintype "passive"))
      (node (ref "SV22") (pin "4") (pinfunction "4_4") (pintype "passive"))
    )
    (net (code "188") (name "Net-(IC11-Pad14)") (class "Default")
      (node (ref "IC11") (pin "14") (pinfunction "14_14") (pintype "passive"))
      (node (ref "SV22") (pin "3") (pinfunction "3_3") (pintype "passive"))
    )
    (net (code "189") (name "Net-(IC11-Pad15)") (class "Default")
      (node (ref "IC11") (pin "15") (pinfunction "15_15") (pintype "passive"))
      (node (ref "SV22") (pin "2") (pinfunction "2_2") (pintype "passive"))
    )
    (net (code "190") (name "Net-(IC12-Pad1)") (class "Default")
      (node (ref "IC12") (pin "1") (pinfunction "1_1") (pintype "passive"))
      (node (ref "SV41") (pin "8") (pinfunction "8_8") (pintype "passive"))
    )
    (net (code "191") (name "Net-(IC12-Pad2)") (class "Default")
      (node (ref "IC12") (pin "2") (pinfunction "2_2") (pintype "passive"))
      (node (ref "SV41") (pin "7") (pinfunction "7_7") (pintype "passive"))
    )
    (net (code "192") (name "Net-(IC12-Pad3)") (class "Default")
      (node (ref "IC12") (pin "3") (pinfunction "3_3") (pintype "passive"))
      (node (ref "SV41") (pin "6") (pinfunction "6_6") (pintype "passive"))
    )
    (net (code "193") (name "Net-(IC12-Pad4)") (class "Default")
      (node (ref "IC12") (pin "4") (pinfunction "4_4") (pintype "passive"))
      (node (ref "SV41") (pin "5") (pinfunction "5_5") (pintype "passive"))
    )
    (net (code "194") (name "Net-(IC12-Pad5)") (class "Default")
      (node (ref "IC12") (pin "5") (pinfunction "5_5") (pintype "passive"))
      (node (ref "SV41") (pin "4") (pinfunction "4_4") (pintype "passive"))
    )
    (net (code "195") (name "Net-(IC12-Pad6)") (class "Default")
      (node (ref "IC12") (pin "6") (pinfunction "6_6") (pintype "passive"))
      (node (ref "SV41") (pin "3") (pinfunction "3_3") (pintype "passive"))
    )
    (net (code "196") (name "Net-(IC12-Pad7)") (class "Default")
      (node (ref "IC12") (pin "7") (pinfunction "7_7") (pintype "passive"))
      (node (ref "SV41") (pin "2") (pinfunction "2_2") (pintype "passive"))
    )
    (net (code "197") (name "Net-(IC12-Pad9)") (class "Default")
      (node (ref "IC12") (pin "9") (pinfunction "9_9") (pintype "passive"))
      (node (ref "SV48") (pin "8") (pinfunction "8_8") (pintype "passive"))
    )
    (net (code "198") (name "Net-(IC12-Pad10)") (class "Default")
      (node (ref "IC12") (pin "10") (pinfunction "10_10") (pintype "passive"))
      (node (ref "SV48") (pin "7") (pinfunction "7_7") (pintype "passive"))
    )
    (net (code "199") (name "Net-(IC12-Pad11)") (class "Default")
      (node (ref "IC12") (pin "11") (pinfunction "11_11") (pintype "passive"))
      (node (ref "SV48") (pin "6") (pinfunction "6_6") (pintype "passive"))
    )
    (net (code "200") (name "Net-(IC12-Pad12)") (class "Default")
      (node (ref "IC12") (pin "12") (pinfunction "12_12") (pintype "passive"))
      (node (ref "SV48") (pin "5") (pinfunction "5_5") (pintype "passive"))
    )
    (net (code "201") (name "Net-(IC12-Pad13)") (class "Default")
      (node (ref "IC12") (pin "13") (pinfunction "13_13") (pintype "passive"))
      (node (ref "SV48") (pin "4") (pinfunction "4_4") (pintype "passive"))
    )
    (net (code "202") (name "Net-(IC12-Pad14)") (class "Default")
      (node (ref "IC12") (pin "14") (pinfunction "14_14") (pintype "passive"))
      (node (ref "SV48") (pin "3") (pinfunction "3_3") (pintype "passive"))
    )
    (net (code "203") (name "Net-(IC12-Pad15)") (class "Default")
      (node (ref "IC12") (pin "15") (pinfunction "15_15") (pintype "passive"))
      (node (ref "SV48") (pin "2") (pinfunction "2_2") (pintype "passive"))
    )
    (net (code "204") (name "Net-(IC13-Pad1)") (class "Default")
      (node (ref "IC13") (pin "1") (pinfunction "1_1") (pintype "passive"))
      (node (ref "SV4") (pin "8") (pinfunction "8_8") (pintype "passive"))
    )
    (net (code "205") (name "Net-(IC13-Pad2)") (class "Default")
      (node (ref "IC13") (pin "2") (pinfunction "2_2") (pintype "passive"))
      (node (ref "SV4") (pin "7") (pinfunction "7_7") (pintype "passive"))
    )
    (net (code "206") (name "Net-(IC13-Pad3)") (class "Default")
      (node (ref "IC13") (pin "3") (pinfunction "3_3") (pintype "passive"))
      (node (ref "SV4") (pin "6") (pinfunction "6_6") (pintype "passive"))
    )
    (net (code "207") (name "Net-(IC13-Pad4)") (class "Default")
      (node (ref "IC13") (pin "4") (pinfunction "4_4") (pintype "passive"))
      (node (ref "SV4") (pin "5") (pinfunction "5_5") (pintype "passive"))
    )
    (net (code "208") (name "Net-(IC13-Pad5)") (class "Default")
      (node (ref "IC13") (pin "5") (pinfunction "5_5") (pintype "passive"))
      (node (ref "SV4") (pin "4") (pinfunction "4_4") (pintype "passive"))
    )
    (net (code "209") (name "Net-(IC13-Pad6)") (class "Default")
      (node (ref "IC13") (pin "6") (pinfunction "6_6") (pintype "passive"))
      (node (ref "SV4") (pin "3") (pinfunction "3_3") (pintype "passive"))
    )
    (net (code "210") (name "Net-(IC13-Pad7)") (class "Default")
      (node (ref "IC13") (pin "7") (pinfunction "7_7") (pintype "passive"))
      (node (ref "SV4") (pin "2") (pinfunction "2_2") (pintype "passive"))
    )
    (net (code "211") (name "Net-(IC13-Pad9)") (class "Default")
      (node (ref "IC13") (pin "9") (pinfunction "9_9") (pintype "passive"))
      (node (ref "SV5") (pin "8") (pinfunction "8_8") (pintype "passive"))
    )
    (net (code "212") (name "Net-(IC13-Pad10)") (class "Default")
      (node (ref "IC13") (pin "10") (pinfunction "10_10") (pintype "passive"))
      (node (ref "SV5") (pin "7") (pinfunction "7_7") (pintype "passive"))
    )
    (net (code "213") (name "Net-(IC13-Pad11)") (class "Default")
      (node (ref "IC13") (pin "11") (pinfunction "11_11") (pintype "passive"))
      (node (ref "SV5") (pin "6") (pinfunction "6_6") (pintype "passive"))
    )
    (net (code "214") (name "Net-(IC13-Pad12)") (class "Default")
      (node (ref "IC13") (pin "12") (pinfunction "12_12") (pintype "passive"))
      (node (ref "SV5") (pin "5") (pinfunction "5_5") (pintype "passive"))
    )
    (net (code "215") (name "Net-(IC13-Pad13)") (class "Default")
      (node (ref "IC13") (pin "13") (pinfunction "13_13") (pintype "passive"))
      (node (ref "SV5") (pin "4") (pinfunction "4_4") (pintype "passive"))
    )
    (net (code "216") (name "Net-(IC13-Pad14)") (class "Default")
      (node (ref "IC13") (pin "14") (pinfunction "14_14") (pintype "passive"))
      (node (ref "SV5") (pin "3") (pinfunction "3_3") (pintype "passive"))
    )
    (net (code "217") (name "Net-(IC13-Pad15)") (class "Default")
      (node (ref "IC13") (pin "15") (pinfunction "15_15") (pintype "passive"))
      (node (ref "SV5") (pin "2") (pinfunction "2_2") (pintype "passive"))
    )
    (net (code "218") (name "Net-(IC14-Pad1)") (class "Default")
      (node (ref "IC14") (pin "1") (pinfunction "1_1") (pintype "passive"))
      (node (ref "SV12") (pin "8") (pinfunction "8_8") (pintype "passive"))
    )
    (net (code "219") (name "Net-(IC14-Pad2)") (class "Default")
      (node (ref "IC14") (pin "2") (pinfunction "2_2") (pintype "passive"))
      (node (ref "SV12") (pin "7") (pinfunction "7_7") (pintype "passive"))
    )
    (net (code "220") (name "Net-(IC14-Pad3)") (class "Default")
      (node (ref "IC14") (pin "3") (pinfunction "3_3") (pintype "passive"))
      (node (ref "SV12") (pin "6") (pinfunction "6_6") (pintype "passive"))
    )
    (net (code "221") (name "Net-(IC14-Pad4)") (class "Default")
      (node (ref "IC14") (pin "4") (pinfunction "4_4") (pintype "passive"))
      (node (ref "SV12") (pin "5") (pinfunction "5_5") (pintype "passive"))
    )
    (net (code "222") (name "Net-(IC14-Pad5)") (class "Default")
      (node (ref "IC14") (pin "5") (pinfunction "5_5") (pintype "passive"))
      (node (ref "SV12") (pin "4") (pinfunction "4_4") (pintype "passive"))
    )
    (net (code "223") (name "Net-(IC14-Pad6)") (class "Default")
      (node (ref "IC14") (pin "6") (pinfunction "6_6") (pintype "passive"))
      (node (ref "SV12") (pin "3") (pinfunction "3_3") (pintype "passive"))
    )
    (net (code "224") (name "Net-(IC14-Pad7)") (class "Default")
      (node (ref "IC14") (pin "7") (pinfunction "7_7") (pintype "passive"))
      (node (ref "SV12") (pin "2") (pinfunction "2_2") (pintype "passive"))
    )
    (net (code "225") (name "Net-(IC14-Pad9)") (class "Default")
      (node (ref "IC14") (pin "9") (pinfunction "9_9") (pintype "passive"))
      (node (ref "SV13") (pin "8") (pinfunction "8_8") (pintype "passive"))
    )
    (net (code "226") (name "Net-(IC14-Pad10)") (class "Default")
      (node (ref "IC14") (pin "10") (pinfunction "10_10") (pintype "passive"))
      (node (ref "SV13") (pin "7") (pinfunction "7_7") (pintype "passive"))
    )
    (net (code "227") (name "Net-(IC14-Pad11)") (class "Default")
      (node (ref "IC14") (pin "11") (pinfunction "11_11") (pintype "passive"))
      (node (ref "SV13") (pin "6") (pinfunction "6_6") (pintype "passive"))
    )
    (net (code "228") (name "Net-(IC14-Pad12)") (class "Default")
      (node (ref "IC14") (pin "12") (pinfunction "12_12") (pintype "passive"))
      (node (ref "SV13") (pin "5") (pinfunction "5_5") (pintype "passive"))
    )
    (net (code "229") (name "Net-(IC14-Pad13)") (class "Default")
      (node (ref "IC14") (pin "13") (pinfunction "13_13") (pintype "passive"))
      (node (ref "SV13") (pin "4") (pinfunction "4_4") (pintype "passive"))
    )
    (net (code "230") (name "Net-(IC14-Pad14)") (class "Default")
      (node (ref "IC14") (pin "14") (pinfunction "14_14") (pintype "passive"))
      (node (ref "SV13") (pin "3") (pinfunction "3_3") (pintype "passive"))
    )
    (net (code "231") (name "Net-(IC14-Pad15)") (class "Default")
      (node (ref "IC14") (pin "15") (pinfunction "15_15") (pintype "passive"))
      (node (ref "SV13") (pin "2") (pinfunction "2_2") (pintype "passive"))
    )
    (net (code "232") (name "Net-(IC15-Pad1)") (class "Default")
      (node (ref "IC15") (pin "1") (pinfunction "1_1") (pintype "passive"))
      (node (ref "SV20") (pin "8") (pinfunction "8_8") (pintype "passive"))
    )
    (net (code "233") (name "Net-(IC15-Pad2)") (class "Default")
      (node (ref "IC15") (pin "2") (pinfunction "2_2") (pintype "passive"))
      (node (ref "SV20") (pin "7") (pinfunction "7_7") (pintype "passive"))
    )
    (net (code "234") (name "Net-(IC15-Pad3)") (class "Default")
      (node (ref "IC15") (pin "3") (pinfunction "3_3") (pintype "passive"))
      (node (ref "SV20") (pin "6") (pinfunction "6_6") (pintype "passive"))
    )
    (net (code "235") (name "Net-(IC15-Pad4)") (class "Default")
      (node (ref "IC15") (pin "4") (pinfunction "4_4") (pintype "passive"))
      (node (ref "SV20") (pin "5") (pinfunction "5_5") (pintype "passive"))
    )
    (net (code "236") (name "Net-(IC15-Pad5)") (class "Default")
      (node (ref "IC15") (pin "5") (pinfunction "5_5") (pintype "passive"))
      (node (ref "SV20") (pin "4") (pinfunction "4_4") (pintype "passive"))
    )
    (net (code "237") (name "Net-(IC15-Pad6)") (class "Default")
      (node (ref "IC15") (pin "6") (pinfunction "6_6") (pintype "passive"))
      (node (ref "SV20") (pin "3") (pinfunction "3_3") (pintype "passive"))
    )
    (net (code "238") (name "Net-(IC15-Pad7)") (class "Default")
      (node (ref "IC15") (pin "7") (pinfunction "7_7") (pintype "passive"))
      (node (ref "SV20") (pin "2") (pinfunction "2_2") (pintype "passive"))
    )
    (net (code "239") (name "Net-(IC15-Pad9)") (class "Default")
      (node (ref "IC15") (pin "9") (pinfunction "9_9") (pintype "passive"))
      (node (ref "SV21") (pin "8") (pinfunction "8_8") (pintype "passive"))
    )
    (net (code "240") (name "Net-(IC15-Pad10)") (class "Default")
      (node (ref "IC15") (pin "10") (pinfunction "10_10") (pintype "passive"))
      (node (ref "SV21") (pin "7") (pinfunction "7_7") (pintype "passive"))
    )
    (net (code "241") (name "Net-(IC15-Pad11)") (class "Default")
      (node (ref "IC15") (pin "11") (pinfunction "11_11") (pintype "passive"))
      (node (ref "SV21") (pin "6") (pinfunction "6_6") (pintype "passive"))
    )
    (net (code "242") (name "Net-(IC15-Pad12)") (class "Default")
      (node (ref "IC15") (pin "12") (pinfunction "12_12") (pintype "passive"))
      (node (ref "SV21") (pin "5") (pinfunction "5_5") (pintype "passive"))
    )
    (net (code "243") (name "Net-(IC15-Pad13)") (class "Default")
      (node (ref "IC15") (pin "13") (pinfunction "13_13") (pintype "passive"))
      (node (ref "SV21") (pin "4") (pinfunction "4_4") (pintype "passive"))
    )
    (net (code "244") (name "Net-(IC15-Pad14)") (class "Default")
      (node (ref "IC15") (pin "14") (pinfunction "14_14") (pintype "passive"))
      (node (ref "SV21") (pin "3") (pinfunction "3_3") (pintype "passive"))
    )
    (net (code "245") (name "Net-(IC15-Pad15)") (class "Default")
      (node (ref "IC15") (pin "15") (pinfunction "15_15") (pintype "passive"))
      (node (ref "SV21") (pin "2") (pinfunction "2_2") (pintype "passive"))
    )
    (net (code "246") (name "Net-(IC16-Pad1)") (class "Default")
      (node (ref "IC16") (pin "1") (pinfunction "1_1") (pintype "passive"))
      (node (ref "SV26") (pin "8") (pinfunction "8_8") (pintype "passive"))
    )
    (net (code "247") (name "Net-(IC16-Pad2)") (class "Default")
      (node (ref "IC16") (pin "2") (pinfunction "2_2") (pintype "passive"))
      (node (ref "SV26") (pin "7") (pinfunction "7_7") (pintype "passive"))
    )
    (net (code "248") (name "Net-(IC16-Pad3)") (class "Default")
      (node (ref "IC16") (pin "3") (pinfunction "3_3") (pintype "passive"))
      (node (ref "SV26") (pin "6") (pinfunction "6_6") (pintype "passive"))
    )
    (net (code "249") (name "Net-(IC16-Pad4)") (class "Default")
      (node (ref "IC16") (pin "4") (pinfunction "4_4") (pintype "passive"))
      (node (ref "SV26") (pin "5") (pinfunction "5_5") (pintype "passive"))
    )
    (net (code "250") (name "Net-(IC16-Pad5)") (class "Default")
      (node (ref "IC16") (pin "5") (pinfunction "5_5") (pintype "passive"))
      (node (ref "SV26") (pin "4") (pinfunction "4_4") (pintype "passive"))
    )
    (net (code "251") (name "Net-(IC16-Pad6)") (class "Default")
      (node (ref "IC16") (pin "6") (pinfunction "6_6") (pintype "passive"))
      (node (ref "SV26") (pin "3") (pinfunction "3_3") (pintype "passive"))
    )
    (net (code "252") (name "Net-(IC16-Pad7)") (class "Default")
      (node (ref "IC16") (pin "7") (pinfunction "7_7") (pintype "passive"))
      (node (ref "SV26") (pin "2") (pinfunction "2_2") (pintype "passive"))
    )
    (net (code "253") (name "Net-(IC16-Pad9)") (class "Default")
      (node (ref "IC16") (pin "9") (pinfunction "9_9") (pintype "passive"))
      (node (ref "SV31") (pin "8") (pinfunction "8_8") (pintype "passive"))
    )
    (net (code "254") (name "Net-(IC16-Pad10)") (class "Default")
      (node (ref "IC16") (pin "10") (pinfunction "10_10") (pintype "passive"))
      (node (ref "SV31") (pin "7") (pinfunction "7_7") (pintype "passive"))
    )
    (net (code "255") (name "Net-(IC16-Pad11)") (class "Default")
      (node (ref "IC16") (pin "11") (pinfunction "11_11") (pintype "passive"))
      (node (ref "SV31") (pin "6") (pinfunction "6_6") (pintype "passive"))
    )
    (net (code "256") (name "Net-(IC16-Pad12)") (class "Default")
      (node (ref "IC16") (pin "12") (pinfunction "12_12") (pintype "passive"))
      (node (ref "SV31") (pin "5") (pinfunction "5_5") (pintype "passive"))
    )
    (net (code "257") (name "Net-(IC16-Pad13)") (class "Default")
      (node (ref "IC16") (pin "13") (pinfunction "13_13") (pintype "passive"))
      (node (ref "SV31") (pin "4") (pinfunction "4_4") (pintype "passive"))
    )
    (net (code "258") (name "Net-(IC16-Pad14)") (class "Default")
      (node (ref "IC16") (pin "14") (pinfunction "14_14") (pintype "passive"))
      (node (ref "SV31") (pin "3") (pinfunction "3_3") (pintype "passive"))
    )
    (net (code "259") (name "Net-(IC16-Pad15)") (class "Default")
      (node (ref "IC16") (pin "15") (pinfunction "15_15") (pintype "passive"))
      (node (ref "SV31") (pin "2") (pinfunction "2_2") (pintype "passive"))
    )
    (net (code "260") (name "Net-(IC17-Pad1)") (class "Default")
      (node (ref "IC17") (pin "1") (pinfunction "1_1") (pintype "passive"))
      (node (ref "SV34") (pin "8") (pinfunction "8_8") (pintype "passive"))
    )
    (net (code "261") (name "Net-(IC17-Pad2)") (class "Default")
      (node (ref "IC17") (pin "2") (pinfunction "2_2") (pintype "passive"))
      (node (ref "SV34") (pin "7") (pinfunction "7_7") (pintype "passive"))
    )
    (net (code "262") (name "Net-(IC17-Pad3)") (class "Default")
      (node (ref "IC17") (pin "3") (pinfunction "3_3") (pintype "passive"))
      (node (ref "SV34") (pin "6") (pinfunction "6_6") (pintype "passive"))
    )
    (net (code "263") (name "Net-(IC17-Pad4)") (class "Default")
      (node (ref "IC17") (pin "4") (pinfunction "4_4") (pintype "passive"))
      (node (ref "SV34") (pin "5") (pinfunction "5_5") (pintype "passive"))
    )
    (net (code "264") (name "Net-(IC17-Pad5)") (class "Default")
      (node (ref "IC17") (pin "5") (pinfunction "5_5") (pintype "passive"))
      (node (ref "SV34") (pin "4") (pinfunction "4_4") (pintype "passive"))
    )
    (net (code "265") (name "Net-(IC17-Pad6)") (class "Default")
      (node (ref "IC17") (pin "6") (pinfunction "6_6") (pintype "passive"))
      (node (ref "SV34") (pin "3") (pinfunction "3_3") (pintype "passive"))
    )
    (net (code "266") (name "Net-(IC17-Pad7)") (class "Default")
      (node (ref "IC17") (pin "7") (pinfunction "7_7") (pintype "passive"))
      (node (ref "SV34") (pin "2") (pinfunction "2_2") (pintype "passive"))
    )
    (net (code "267") (name "Net-(IC17-Pad9)") (class "Default")
      (node (ref "IC17") (pin "9") (pinfunction "9_9") (pintype "passive"))
      (node (ref "SV39") (pin "8") (pinfunction "8_8") (pintype "passive"))
    )
    (net (code "268") (name "Net-(IC17-Pad10)") (class "Default")
      (node (ref "IC17") (pin "10") (pinfunction "10_10") (pintype "passive"))
      (node (ref "SV39") (pin "7") (pinfunction "7_7") (pintype "passive"))
    )
    (net (code "269") (name "Net-(IC17-Pad11)") (class "Default")
      (node (ref "IC17") (pin "11") (pinfunction "11_11") (pintype "passive"))
      (node (ref "SV39") (pin "6") (pinfunction "6_6") (pintype "passive"))
    )
    (net (code "270") (name "Net-(IC17-Pad12)") (class "Default")
      (node (ref "IC17") (pin "12") (pinfunction "12_12") (pintype "passive"))
      (node (ref "SV39") (pin "5") (pinfunction "5_5") (pintype "passive"))
    )
    (net (code "271") (name "Net-(IC17-Pad13)") (class "Default")
      (node (ref "IC17") (pin "13") (pinfunction "13_13") (pintype "passive"))
      (node (ref "SV39") (pin "4") (pinfunction "4_4") (pintype "passive"))
    )
    (net (code "272") (name "Net-(IC17-Pad14)") (class "Default")
      (node (ref "IC17") (pin "14") (pinfunction "14_14") (pintype "passive"))
      (node (ref "SV39") (pin "3") (pinfunction "3_3") (pintype "passive"))
    )
    (net (code "273") (name "Net-(IC17-Pad15)") (class "Default")
      (node (ref "IC17") (pin "15") (pinfunction "15_15") (pintype "passive"))
      (node (ref "SV39") (pin "2") (pinfunction "2_2") (pintype "passive"))
    )
    (net (code "274") (name "Net-(IC18-Pad1)") (class "Default")
      (node (ref "IC18") (pin "1") (pinfunction "1_1") (pintype "passive"))
      (node (ref "SV42") (pin "8") (pinfunction "8_8") (pintype "passive"))
    )
    (net (code "275") (name "Net-(IC18-Pad2)") (class "Default")
      (node (ref "IC18") (pin "2") (pinfunction "2_2") (pintype "passive"))
      (node (ref "SV42") (pin "7") (pinfunction "7_7") (pintype "passive"))
    )
    (net (code "276") (name "Net-(IC18-Pad3)") (class "Default")
      (node (ref "IC18") (pin "3") (pinfunction "3_3") (pintype "passive"))
      (node (ref "SV42") (pin "6") (pinfunction "6_6") (pintype "passive"))
    )
    (net (code "277") (name "Net-(IC18-Pad4)") (class "Default")
      (node (ref "IC18") (pin "4") (pinfunction "4_4") (pintype "passive"))
      (node (ref "SV42") (pin "5") (pinfunction "5_5") (pintype "passive"))
    )
    (net (code "278") (name "Net-(IC18-Pad5)") (class "Default")
      (node (ref "IC18") (pin "5") (pinfunction "5_5") (pintype "passive"))
      (node (ref "SV42") (pin "4") (pinfunction "4_4") (pintype "passive"))
    )
    (net (code "279") (name "Net-(IC18-Pad6)") (class "Default")
      (node (ref "IC18") (pin "6") (pinfunction "6_6") (pintype "passive"))
      (node (ref "SV42") (pin "3") (pinfunction "3_3") (pintype "passive"))
    )
    (net (code "280") (name "Net-(IC18-Pad7)") (class "Default")
      (node (ref "IC18") (pin "7") (pinfunction "7_7") (pintype "passive"))
      (node (ref "SV42") (pin "2") (pinfunction "2_2") (pintype "passive"))
    )
    (net (code "281") (name "Net-(IC18-Pad9)") (class "Default")
      (node (ref "IC18") (pin "9") (pinfunction "9_9") (pintype "passive"))
      (node (ref "SV47") (pin "8") (pinfunction "8_8") (pintype "passive"))
    )
    (net (code "282") (name "Net-(IC18-Pad10)") (class "Default")
      (node (ref "IC18") (pin "10") (pinfunction "10_10") (pintype "passive"))
      (node (ref "SV47") (pin "7") (pinfunction "7_7") (pintype "passive"))
    )
    (net (code "283") (name "Net-(IC18-Pad11)") (class "Default")
      (node (ref "IC18") (pin "11") (pinfunction "11_11") (pintype "passive"))
      (node (ref "SV47") (pin "6") (pinfunction "6_6") (pintype "passive"))
    )
    (net (code "284") (name "Net-(IC18-Pad12)") (class "Default")
      (node (ref "IC18") (pin "12") (pinfunction "12_12") (pintype "passive"))
      (node (ref "SV47") (pin "5") (pinfunction "5_5") (pintype "passive"))
    )
    (net (code "285") (name "Net-(IC18-Pad13)") (class "Default")
      (node (ref "IC18") (pin "13") (pinfunction "13_13") (pintype "passive"))
      (node (ref "SV47") (pin "4") (pinfunction "4_4") (pintype "passive"))
    )
    (net (code "286") (name "Net-(IC18-Pad14)") (class "Default")
      (node (ref "IC18") (pin "14") (pinfunction "14_14") (pintype "passive"))
      (node (ref "SV47") (pin "3") (pinfunction "3_3") (pintype "passive"))
    )
    (net (code "287") (name "Net-(IC18-Pad15)") (class "Default")
      (node (ref "IC18") (pin "15") (pinfunction "15_15") (pintype "passive"))
      (node (ref "SV47") (pin "2") (pinfunction "2_2") (pintype "passive"))
    )
    (net (code "288") (name "Net-(IC19-Pad1)") (class "Default")
      (node (ref "IC19") (pin "1") (pinfunction "1_1") (pintype "passive"))
      (node (ref "SV27") (pin "8") (pinfunction "8_8") (pintype "passive"))
    )
    (net (code "289") (name "Net-(IC19-Pad2)") (class "Default")
      (node (ref "IC19") (pin "2") (pinfunction "2_2") (pintype "passive"))
      (node (ref "SV27") (pin "7") (pinfunction "7_7") (pintype "passive"))
    )
    (net (code "290") (name "Net-(IC19-Pad3)") (class "Default")
      (node (ref "IC19") (pin "3") (pinfunction "3_3") (pintype "passive"))
      (node (ref "SV27") (pin "6") (pinfunction "6_6") (pintype "passive"))
    )
    (net (code "291") (name "Net-(IC19-Pad4)") (class "Default")
      (node (ref "IC19") (pin "4") (pinfunction "4_4") (pintype "passive"))
      (node (ref "SV27") (pin "5") (pinfunction "5_5") (pintype "passive"))
    )
    (net (code "292") (name "Net-(IC19-Pad5)") (class "Default")
      (node (ref "IC19") (pin "5") (pinfunction "5_5") (pintype "passive"))
      (node (ref "SV27") (pin "4") (pinfunction "4_4") (pintype "passive"))
    )
    (net (code "293") (name "Net-(IC19-Pad6)") (class "Default")
      (node (ref "IC19") (pin "6") (pinfunction "6_6") (pintype "passive"))
      (node (ref "SV27") (pin "3") (pinfunction "3_3") (pintype "passive"))
    )
    (net (code "294") (name "Net-(IC19-Pad7)") (class "Default")
      (node (ref "IC19") (pin "7") (pinfunction "7_7") (pintype "passive"))
      (node (ref "SV27") (pin "2") (pinfunction "2_2") (pintype "passive"))
    )
    (net (code "295") (name "Net-(IC19-Pad9)") (class "Default")
      (node (ref "IC19") (pin "9") (pinfunction "9_9") (pintype "passive"))
      (node (ref "SV30") (pin "8") (pinfunction "8_8") (pintype "passive"))
    )
    (net (code "296") (name "Net-(IC19-Pad10)") (class "Default")
      (node (ref "IC19") (pin "10") (pinfunction "10_10") (pintype "passive"))
      (node (ref "SV30") (pin "7") (pinfunction "7_7") (pintype "passive"))
    )
    (net (code "297") (name "Net-(IC19-Pad11)") (class "Default")
      (node (ref "IC19") (pin "11") (pinfunction "11_11") (pintype "passive"))
      (node (ref "SV30") (pin "6") (pinfunction "6_6") (pintype "passive"))
    )
    (net (code "298") (name "Net-(IC19-Pad12)") (class "Default")
      (node (ref "IC19") (pin "12") (pinfunction "12_12") (pintype "passive"))
      (node (ref "SV30") (pin "5") (pinfunction "5_5") (pintype "passive"))
    )
    (net (code "299") (name "Net-(IC19-Pad13)") (class "Default")
      (node (ref "IC19") (pin "13") (pinfunction "13_13") (pintype "passive"))
      (node (ref "SV30") (pin "4") (pinfunction "4_4") (pintype "passive"))
    )
    (net (code "300") (name "Net-(IC19-Pad14)") (class "Default")
      (node (ref "IC19") (pin "14") (pinfunction "14_14") (pintype "passive"))
      (node (ref "SV30") (pin "3") (pinfunction "3_3") (pintype "passive"))
    )
    (net (code "301") (name "Net-(IC19-Pad15)") (class "Default")
      (node (ref "IC19") (pin "15") (pinfunction "15_15") (pintype "passive"))
      (node (ref "SV30") (pin "2") (pinfunction "2_2") (pintype "passive"))
    )
    (net (code "302") (name "Net-(IC20-Pad1)") (class "Default")
      (node (ref "IC20") (pin "1") (pinfunction "1_1") (pintype "passive"))
      (node (ref "SV35") (pin "8") (pinfunction "8_8") (pintype "passive"))
    )
    (net (code "303") (name "Net-(IC20-Pad2)") (class "Default")
      (node (ref "IC20") (pin "2") (pinfunction "2_2") (pintype "passive"))
      (node (ref "SV35") (pin "7") (pinfunction "7_7") (pintype "passive"))
    )
    (net (code "304") (name "Net-(IC20-Pad3)") (class "Default")
      (node (ref "IC20") (pin "3") (pinfunction "3_3") (pintype "passive"))
      (node (ref "SV35") (pin "6") (pinfunction "6_6") (pintype "passive"))
    )
    (net (code "305") (name "Net-(IC20-Pad4)") (class "Default")
      (node (ref "IC20") (pin "4") (pinfunction "4_4") (pintype "passive"))
      (node (ref "SV35") (pin "5") (pinfunction "5_5") (pintype "passive"))
    )
    (net (code "306") (name "Net-(IC20-Pad5)") (class "Default")
      (node (ref "IC20") (pin "5") (pinfunction "5_5") (pintype "passive"))
      (node (ref "SV35") (pin "4") (pinfunction "4_4") (pintype "passive"))
    )
    (net (code "307") (name "Net-(IC20-Pad6)") (class "Default")
      (node (ref "IC20") (pin "6") (pinfunction "6_6") (pintype "passive"))
      (node (ref "SV35") (pin "3") (pinfunction "3_3") (pintype "passive"))
    )
    (net (code "308") (name "Net-(IC20-Pad7)") (class "Default")
      (node (ref "IC20") (pin "7") (pinfunction "7_7") (pintype "passive"))
      (node (ref "SV35") (pin "2") (pinfunction "2_2") (pintype "passive"))
    )
    (net (code "309") (name "Net-(IC20-Pad9)") (class "Default")
      (node (ref "IC20") (pin "9") (pinfunction "9_9") (pintype "passive"))
      (node (ref "SV38") (pin "8") (pinfunction "8_8") (pintype "passive"))
    )
    (net (code "310") (name "Net-(IC20-Pad10)") (class "Default")
      (node (ref "IC20") (pin "10") (pinfunction "10_10") (pintype "passive"))
      (node (ref "SV38") (pin "7") (pinfunction "7_7") (pintype "passive"))
    )
    (net (code "311") (name "Net-(IC20-Pad11)") (class "Default")
      (node (ref "IC20") (pin "11") (pinfunction "11_11") (pintype "passive"))
      (node (ref "SV38") (pin "6") (pinfunction "6_6") (pintype "passive"))
    )
    (net (code "312") (name "Net-(IC20-Pad12)") (class "Default")
      (node (ref "IC20") (pin "12") (pinfunction "12_12") (pintype "passive"))
      (node (ref "SV38") (pin "5") (pinfunction "5_5") (pintype "passive"))
    )
    (net (code "313") (name "Net-(IC20-Pad13)") (class "Default")
      (node (ref "IC20") (pin "13") (pinfunction "13_13") (pintype "passive"))
      (node (ref "SV38") (pin "4") (pinfunction "4_4") (pintype "passive"))
    )
    (net (code "314") (name "Net-(IC20-Pad14)") (class "Default")
      (node (ref "IC20") (pin "14") (pinfunction "14_14") (pintype "passive"))
      (node (ref "SV38") (pin "3") (pinfunction "3_3") (pintype "passive"))
    )
    (net (code "315") (name "Net-(IC20-Pad15)") (class "Default")
      (node (ref "IC20") (pin "15") (pinfunction "15_15") (pintype "passive"))
      (node (ref "SV38") (pin "2") (pinfunction "2_2") (pintype "passive"))
    )
    (net (code "316") (name "Net-(IC21-Pad1)") (class "Default")
      (node (ref "IC21") (pin "1") (pinfunction "1_1") (pintype "passive"))
      (node (ref "SV43") (pin "8") (pinfunction "8_8") (pintype "passive"))
    )
    (net (code "317") (name "Net-(IC21-Pad2)") (class "Default")
      (node (ref "IC21") (pin "2") (pinfunction "2_2") (pintype "passive"))
      (node (ref "SV43") (pin "7") (pinfunction "7_7") (pintype "passive"))
    )
    (net (code "318") (name "Net-(IC21-Pad3)") (class "Default")
      (node (ref "IC21") (pin "3") (pinfunction "3_3") (pintype "passive"))
      (node (ref "SV43") (pin "6") (pinfunction "6_6") (pintype "passive"))
    )
    (net (code "319") (name "Net-(IC21-Pad4)") (class "Default")
      (node (ref "IC21") (pin "4") (pinfunction "4_4") (pintype "passive"))
      (node (ref "SV43") (pin "5") (pinfunction "5_5") (pintype "passive"))
    )
    (net (code "320") (name "Net-(IC21-Pad5)") (class "Default")
      (node (ref "IC21") (pin "5") (pinfunction "5_5") (pintype "passive"))
      (node (ref "SV43") (pin "4") (pinfunction "4_4") (pintype "passive"))
    )
    (net (code "321") (name "Net-(IC21-Pad6)") (class "Default")
      (node (ref "IC21") (pin "6") (pinfunction "6_6") (pintype "passive"))
      (node (ref "SV43") (pin "3") (pinfunction "3_3") (pintype "passive"))
    )
    (net (code "322") (name "Net-(IC21-Pad7)") (class "Default")
      (node (ref "IC21") (pin "7") (pinfunction "7_7") (pintype "passive"))
      (node (ref "SV43") (pin "2") (pinfunction "2_2") (pintype "passive"))
    )
    (net (code "323") (name "Net-(IC21-Pad9)") (class "Default")
      (node (ref "IC21") (pin "9") (pinfunction "9_9") (pintype "passive"))
      (node (ref "SV46") (pin "8") (pinfunction "8_8") (pintype "passive"))
    )
    (net (code "324") (name "Net-(IC21-Pad10)") (class "Default")
      (node (ref "IC21") (pin "10") (pinfunction "10_10") (pintype "passive"))
      (node (ref "SV46") (pin "7") (pinfunction "7_7") (pintype "passive"))
    )
    (net (code "325") (name "Net-(IC21-Pad11)") (class "Default")
      (node (ref "IC21") (pin "11") (pinfunction "11_11") (pintype "passive"))
      (node (ref "SV46") (pin "6") (pinfunction "6_6") (pintype "passive"))
    )
    (net (code "326") (name "Net-(IC21-Pad12)") (class "Default")
      (node (ref "IC21") (pin "12") (pinfunction "12_12") (pintype "passive"))
      (node (ref "SV46") (pin "5") (pinfunction "5_5") (pintype "passive"))
    )
    (net (code "327") (name "Net-(IC21-Pad13)") (class "Default")
      (node (ref "IC21") (pin "13") (pinfunction "13_13") (pintype "passive"))
      (node (ref "SV46") (pin "4") (pinfunction "4_4") (pintype "passive"))
    )
    (net (code "328") (name "Net-(IC21-Pad14)") (class "Default")
      (node (ref "IC21") (pin "14") (pinfunction "14_14") (pintype "passive"))
      (node (ref "SV46") (pin "3") (pinfunction "3_3") (pintype "passive"))
    )
    (net (code "329") (name "Net-(IC21-Pad15)") (class "Default")
      (node (ref "IC21") (pin "15") (pinfunction "15_15") (pintype "passive"))
      (node (ref "SV46") (pin "2") (pinfunction "2_2") (pintype "passive"))
    )
    (net (code "330") (name "Net-(IC22-Pad1)") (class "Default")
      (node (ref "IC22") (pin "1") (pinfunction "1_1") (pintype "passive"))
      (node (ref "SV28") (pin "8") (pinfunction "8_8") (pintype "passive"))
    )
    (net (code "331") (name "Net-(IC22-Pad2)") (class "Default")
      (node (ref "IC22") (pin "2") (pinfunction "2_2") (pintype "passive"))
      (node (ref "SV28") (pin "7") (pinfunction "7_7") (pintype "passive"))
    )
    (net (code "332") (name "Net-(IC22-Pad3)") (class "Default")
      (node (ref "IC22") (pin "3") (pinfunction "3_3") (pintype "passive"))
      (node (ref "SV28") (pin "6") (pinfunction "6_6") (pintype "passive"))
    )
    (net (code "333") (name "Net-(IC22-Pad4)") (class "Default")
      (node (ref "IC22") (pin "4") (pinfunction "4_4") (pintype "passive"))
      (node (ref "SV28") (pin "5") (pinfunction "5_5") (pintype "passive"))
    )
    (net (code "334") (name "Net-(IC22-Pad5)") (class "Default")
      (node (ref "IC22") (pin "5") (pinfunction "5_5") (pintype "passive"))
      (node (ref "SV28") (pin "4") (pinfunction "4_4") (pintype "passive"))
    )
    (net (code "335") (name "Net-(IC22-Pad6)") (class "Default")
      (node (ref "IC22") (pin "6") (pinfunction "6_6") (pintype "passive"))
      (node (ref "SV28") (pin "3") (pinfunction "3_3") (pintype "passive"))
    )
    (net (code "336") (name "Net-(IC22-Pad7)") (class "Default")
      (node (ref "IC22") (pin "7") (pinfunction "7_7") (pintype "passive"))
      (node (ref "SV28") (pin "2") (pinfunction "2_2") (pintype "passive"))
    )
    (net (code "337") (name "Net-(IC22-Pad9)") (class "Default")
      (node (ref "IC22") (pin "9") (pinfunction "9_9") (pintype "passive"))
      (node (ref "SV29") (pin "8") (pinfunction "8_8") (pintype "passive"))
    )
    (net (code "338") (name "Net-(IC22-Pad10)") (class "Default")
      (node (ref "IC22") (pin "10") (pinfunction "10_10") (pintype "passive"))
      (node (ref "SV29") (pin "7") (pinfunction "7_7") (pintype "passive"))
    )
    (net (code "339") (name "Net-(IC22-Pad11)") (class "Default")
      (node (ref "IC22") (pin "11") (pinfunction "11_11") (pintype "passive"))
      (node (ref "SV29") (pin "6") (pinfunction "6_6") (pintype "passive"))
    )
    (net (code "340") (name "Net-(IC22-Pad12)") (class "Default")
      (node (ref "IC22") (pin "12") (pinfunction "12_12") (pintype "passive"))
      (node (ref "SV29") (pin "5") (pinfunction "5_5") (pintype "passive"))
    )
    (net (code "341") (name "Net-(IC22-Pad13)") (class "Default")
      (node (ref "IC22") (pin "13") (pinfunction "13_13") (pintype "passive"))
      (node (ref "SV29") (pin "4") (pinfunction "4_4") (pintype "passive"))
    )
    (net (code "342") (name "Net-(IC22-Pad14)") (class "Default")
      (node (ref "IC22") (pin "14") (pinfunction "14_14") (pintype "passive"))
      (node (ref "SV29") (pin "3") (pinfunction "3_3") (pintype "passive"))
    )
    (net (code "343") (name "Net-(IC22-Pad15)") (class "Default")
      (node (ref "IC22") (pin "15") (pinfunction "15_15") (pintype "passive"))
      (node (ref "SV29") (pin "2") (pinfunction "2_2") (pintype "passive"))
    )
    (net (code "344") (name "Net-(IC23-Pad1)") (class "Default")
      (node (ref "IC23") (pin "1") (pinfunction "1_1") (pintype "passive"))
      (node (ref "SV36") (pin "8") (pinfunction "8_8") (pintype "passive"))
    )
    (net (code "345") (name "Net-(IC23-Pad2)") (class "Default")
      (node (ref "IC23") (pin "2") (pinfunction "2_2") (pintype "passive"))
      (node (ref "SV36") (pin "7") (pinfunction "7_7") (pintype "passive"))
    )
    (net (code "346") (name "Net-(IC23-Pad3)") (class "Default")
      (node (ref "IC23") (pin "3") (pinfunction "3_3") (pintype "passive"))
      (node (ref "SV36") (pin "6") (pinfunction "6_6") (pintype "passive"))
    )
    (net (code "347") (name "Net-(IC23-Pad4)") (class "Default")
      (node (ref "IC23") (pin "4") (pinfunction "4_4") (pintype "passive"))
      (node (ref "SV36") (pin "5") (pinfunction "5_5") (pintype "passive"))
    )
    (net (code "348") (name "Net-(IC23-Pad5)") (class "Default")
      (node (ref "IC23") (pin "5") (pinfunction "5_5") (pintype "passive"))
      (node (ref "SV36") (pin "4") (pinfunction "4_4") (pintype "passive"))
    )
    (net (code "349") (name "Net-(IC23-Pad6)") (class "Default")
      (node (ref "IC23") (pin "6") (pinfunction "6_6") (pintype "passive"))
      (node (ref "SV36") (pin "3") (pinfunction "3_3") (pintype "passive"))
    )
    (net (code "350") (name "Net-(IC23-Pad7)") (class "Default")
      (node (ref "IC23") (pin "7") (pinfunction "7_7") (pintype "passive"))
      (node (ref "SV36") (pin "2") (pinfunction "2_2") (pintype "passive"))
    )
    (net (code "351") (name "Net-(IC23-Pad9)") (class "Default")
      (node (ref "IC23") (pin "9") (pinfunction "9_9") (pintype "passive"))
      (node (ref "SV37") (pin "8") (pinfunction "8_8") (pintype "passive"))
    )
    (net (code "352") (name "Net-(IC23-Pad10)") (class "Default")
      (node (ref "IC23") (pin "10") (pinfunction "10_10") (pintype "passive"))
      (node (ref "SV37") (pin "7") (pinfunction "7_7") (pintype "passive"))
    )
    (net (code "353") (name "Net-(IC23-Pad11)") (class "Default")
      (node (ref "IC23") (pin "11") (pinfunction "11_11") (pintype "passive"))
      (node (ref "SV37") (pin "6") (pinfunction "6_6") (pintype "passive"))
    )
    (net (code "354") (name "Net-(IC23-Pad12)") (class "Default")
      (node (ref "IC23") (pin "12") (pinfunction "12_12") (pintype "passive"))
      (node (ref "SV37") (pin "5") (pinfunction "5_5") (pintype "passive"))
    )
    (net (code "355") (name "Net-(IC23-Pad13)") (class "Default")
      (node (ref "IC23") (pin "13") (pinfunction "13_13") (pintype "passive"))
      (node (ref "SV37") (pin "4") (pinfunction "4_4") (pintype "passive"))
    )
    (net (code "356") (name "Net-(IC23-Pad14)") (class "Default")
      (node (ref "IC23") (pin "14") (pinfunction "14_14") (pintype "passive"))
      (node (ref "SV37") (pin "3") (pinfunction "3_3") (pintype "passive"))
    )
    (net (code "357") (name "Net-(IC23-Pad15)") (class "Default")
      (node (ref "IC23") (pin "15") (pinfunction "15_15") (pintype "passive"))
      (node (ref "SV37") (pin "2") (pinfunction "2_2") (pintype "passive"))
    )
    (net (code "358") (name "Net-(IC24-Pad1)") (class "Default")
      (node (ref "IC24") (pin "1") (pinfunction "1_1") (pintype "passive"))
      (node (ref "SV44") (pin "8") (pinfunction "8_8") (pintype "passive"))
    )
    (net (code "359") (name "Net-(IC24-Pad2)") (class "Default")
      (node (ref "IC24") (pin "2") (pinfunction "2_2") (pintype "passive"))
      (node (ref "SV44") (pin "7") (pinfunction "7_7") (pintype "passive"))
    )
    (net (code "360") (name "Net-(IC24-Pad3)") (class "Default")
      (node (ref "IC24") (pin "3") (pinfunction "3_3") (pintype "passive"))
      (node (ref "SV44") (pin "6") (pinfunction "6_6") (pintype "passive"))
    )
    (net (code "361") (name "Net-(IC24-Pad4)") (class "Default")
      (node (ref "IC24") (pin "4") (pinfunction "4_4") (pintype "passive"))
      (node (ref "SV44") (pin "5") (pinfunction "5_5") (pintype "passive"))
    )
    (net (code "362") (name "Net-(IC24-Pad5)") (class "Default")
      (node (ref "IC24") (pin "5") (pinfunction "5_5") (pintype "passive"))
      (node (ref "SV44") (pin "4") (pinfunction "4_4") (pintype "passive"))
    )
    (net (code "363") (name "Net-(IC24-Pad6)") (class "Default")
      (node (ref "IC24") (pin "6") (pinfunction "6_6") (pintype "passive"))
      (node (ref "SV44") (pin "3") (pinfunction "3_3") (pintype "passive"))
    )
    (net (code "364") (name "Net-(IC24-Pad7)") (class "Default")
      (node (ref "IC24") (pin "7") (pinfunction "7_7") (pintype "passive"))
      (node (ref "SV44") (pin "2") (pinfunction "2_2") (pintype "passive"))
    )
    (net (code "365") (name "Net-(IC24-Pad9)") (class "Default")
      (node (ref "IC24") (pin "9") (pinfunction "9_9") (pintype "passive"))
      (node (ref "SV45") (pin "8") (pinfunction "8_8") (pintype "passive"))
    )
    (net (code "366") (name "Net-(IC24-Pad10)") (class "Default")
      (node (ref "IC24") (pin "10") (pinfunction "10_10") (pintype "passive"))
      (node (ref "SV45") (pin "7") (pinfunction "7_7") (pintype "passive"))
    )
    (net (code "367") (name "Net-(IC24-Pad11)") (class "Default")
      (node (ref "IC24") (pin "11") (pinfunction "11_11") (pintype "passive"))
      (node (ref "SV45") (pin "6") (pinfunction "6_6") (pintype "passive"))
    )
    (net (code "368") (name "Net-(IC24-Pad12)") (class "Default")
      (node (ref "IC24") (pin "12") (pinfunction "12_12") (pintype "passive"))
      (node (ref "SV45") (pin "5") (pinfunction "5_5") (pintype "passive"))
    )
    (net (code "369") (name "Net-(IC24-Pad13)") (class "Default")
      (node (ref "IC24") (pin "13") (pinfunction "13_13") (pintype "passive"))
      (node (ref "SV45") (pin "4") (pinfunction "4_4") (pintype "passive"))
    )
    (net (code "370") (name "Net-(IC24-Pad14)") (class "Default")
      (node (ref "IC24") (pin "14") (pinfunction "14_14") (pintype "passive"))
      (node (ref "SV45") (pin "3") (pinfunction "3_3") (pintype "passive"))
    )
    (net (code "371") (name "Net-(IC24-Pad15)") (class "Default")
      (node (ref "IC24") (pin "15") (pinfunction "15_15") (pintype "passive"))
      (node (ref "SV45") (pin "2") (pinfunction "2_2") (pintype "passive"))
    )
    (net (code "372") (name "Net-(U$2A-1)") (class "Default")
      (node (ref "U$2") (pin "A1") (pinfunction "1_A1") (pintype "bidirectional"))
      (node (ref "U$6") (pin "1") (pinfunction "1_1") (pintype "passive"))
    )
    (net (code "373") (name "Net-(U$2AA-1)") (class "Default")
      (node (ref "U$2") (pin "R1") (pinfunction "1_R1") (pintype "bidirectional"))
      (node (ref "U$6") (pin "14") (pinfunction "14_14") (pintype "passive"))
    )
    (net (code "374") (name "Net-(U$2AB-1)") (class "Default")
      (node (ref "U$2") (pin "R2") (pinfunction "1_R2") (pintype "bidirectional"))
      (node (ref "U$7") (pin "14") (pinfunction "14_14") (pintype "passive"))
    )
    (net (code "375") (name "Net-(U$2AC-1)") (class "Default")
      (node (ref "U$2") (pin "S1") (pinfunction "1_S1") (pintype "bidirectional"))
      (node (ref "U$6") (pin "15") (pinfunction "15_15") (pintype "passive"))
    )
    (net (code "376") (name "Net-(U$2AD-1)") (class "Default")
      (node (ref "U$2") (pin "S2") (pinfunction "1_S2") (pintype "bidirectional"))
      (node (ref "U$7") (pin "15") (pinfunction "15_15") (pintype "passive"))
    )
    (net (code "377") (name "Net-(U$2AE-1)") (class "Default")
      (node (ref "U$2") (pin "T1") (pinfunction "1_T1") (pintype "bidirectional"))
      (node (ref "U$6") (pin "16") (pinfunction "16_16") (pintype "passive"))
    )
    (net (code "378") (name "Net-(U$2AF-1)") (class "Default")
      (node (ref "U$2") (pin "T2") (pinfunction "1_T2") (pintype "bidirectional"))
      (node (ref "U$7") (pin "16") (pinfunction "16_16") (pintype "passive"))
    )
    (net (code "379") (name "Net-(U$2AG-1)") (class "Default")
      (node (ref "U$2") (pin "U1") (pinfunction "1_U1") (pintype "bidirectional"))
      (node (ref "U$6") (pin "17") (pinfunction "17_17") (pintype "passive"))
    )
    (net (code "380") (name "Net-(U$2AH-1)") (class "Default")
      (node (ref "U$2") (pin "U2") (pinfunction "1_U2") (pintype "bidirectional"))
      (node (ref "U$7") (pin "17") (pinfunction "17_17") (pintype "passive"))
    )
    (net (code "381") (name "Net-(U$2AI-1)") (class "Default")
      (node (ref "U$2") (pin "V1") (pinfunction "1_V1") (pintype "bidirectional"))
      (node (ref "U$6") (pin "18") (pinfunction "18_18") (pintype "passive"))
    )
    (net (code "382") (name "Net-(U$2AJ-1)") (class "Default")
      (node (ref "U$2") (pin "V2") (pinfunction "1_V2") (pintype "bidirectional"))
      (node (ref "U$7") (pin "18") (pinfunction "18_18") (pintype "passive"))
    )
    (net (code "383") (name "Net-(U$2B-1)") (class "Default")
      (node (ref "U$2") (pin "A2") (pinfunction "1_A2") (pintype "bidirectional"))
      (node (ref "U$7") (pin "1") (pinfunction "1_1") (pintype "passive"))
    )
    (net (code "384") (name "Net-(U$2C-1)") (class "Default")
      (node (ref "U$2") (pin "B1") (pinfunction "1_B1") (pintype "bidirectional"))
      (node (ref "U$6") (pin "2") (pinfunction "2_2") (pintype "passive"))
    )
    (net (code "385") (name "Net-(U$2D-1)") (class "Default")
      (node (ref "U$2") (pin "B2") (pinfunction "1_B2") (pintype "bidirectional"))
      (node (ref "U$7") (pin "2") (pinfunction "2_2") (pintype "passive"))
    )
    (net (code "386") (name "Net-(U$2E-1)") (class "Default")
      (node (ref "U$2") (pin "C1") (pinfunction "1_C1") (pintype "bidirectional"))
      (node (ref "U$6") (pin "3") (pinfunction "3_3") (pintype "passive"))
    )
    (net (code "387") (name "Net-(U$2F-1)") (class "Default")
      (node (ref "U$2") (pin "C2") (pinfunction "1_C2") (pintype "bidirectional"))
      (node (ref "U$7") (pin "3") (pinfunction "3_3") (pintype "passive"))
    )
    (net (code "388") (name "Net-(U$2G-1)") (class "Default")
      (node (ref "U$2") (pin "D1") (pinfunction "1_D1") (pintype "bidirectional"))
      (node (ref "U$6") (pin "4") (pinfunction "4_4") (pintype "passive"))
    )
    (net (code "389") (name "Net-(U$2H-1)") (class "Default")
      (node (ref "U$2") (pin "D2") (pinfunction "1_D2") (pintype "bidirectional"))
      (node (ref "U$7") (pin "4") (pinfunction "4_4") (pintype "passive"))
    )
    (net (code "390") (name "Net-(U$2I-1)") (class "Default")
      (node (ref "U$2") (pin "E1") (pinfunction "1_E1") (pintype "bidirectional"))
      (node (ref "U$6") (pin "5") (pinfunction "5_5") (pintype "passive"))
    )
    (net (code "391") (name "Net-(U$2J-1)") (class "Default")
      (node (ref "U$2") (pin "E2") (pinfunction "1_E2") (pintype "bidirectional"))
      (node (ref "U$7") (pin "5") (pinfunction "5_5") (pintype "passive"))
    )
    (net (code "392") (name "Net-(U$2K-1)") (class "Default")
      (node (ref "U$2") (pin "F1") (pinfunction "1_F1") (pintype "bidirectional"))
      (node (ref "U$6") (pin "6") (pinfunction "6_6") (pintype "passive"))
    )
    (net (code "393") (name "Net-(U$2L-1)") (class "Default")
      (node (ref "U$2") (pin "F2") (pinfunction "1_F2") (pintype "bidirectional"))
      (node (ref "U$7") (pin "6") (pinfunction "6_6") (pintype "passive"))
    )
    (net (code "394") (name "Net-(U$2M-1)") (class "Default")
      (node (ref "U$2") (pin "H1") (pinfunction "1_H1") (pintype "bidirectional"))
      (node (ref "U$6") (pin "7") (pinfunction "7_7") (pintype "passive"))
    )
    (net (code "395") (name "Net-(U$2N-1)") (class "Default")
      (node (ref "U$2") (pin "H2") (pinfunction "1_H2") (pintype "bidirectional"))
      (node (ref "U$7") (pin "7") (pinfunction "7_7") (pintype "passive"))
    )
    (net (code "396") (name "Net-(U$2O-1)") (class "Default")
      (node (ref "U$2") (pin "J1") (pinfunction "1_J1") (pintype "bidirectional"))
      (node (ref "U$6") (pin "8") (pinfunction "8_8") (pintype "passive"))
    )
    (net (code "397") (name "Net-(U$2P-1)") (class "Default")
      (node (ref "U$2") (pin "J2") (pinfunction "1_J2") (pintype "bidirectional"))
      (node (ref "U$7") (pin "8") (pinfunction "8_8") (pintype "passive"))
    )
    (net (code "398") (name "Net-(U$2Q-1)") (class "Default")
      (node (ref "U$2") (pin "K1") (pinfunction "1_K1") (pintype "bidirectional"))
      (node (ref "U$6") (pin "9") (pinfunction "9_9") (pintype "passive"))
    )
    (net (code "399") (name "Net-(U$2R-1)") (class "Default")
      (node (ref "U$2") (pin "K2") (pinfunction "1_K2") (pintype "bidirectional"))
      (node (ref "U$7") (pin "9") (pinfunction "9_9") (pintype "passive"))
    )
    (net (code "400") (name "Net-(U$2S-1)") (class "Default")
      (node (ref "U$2") (pin "L1") (pinfunction "1_L1") (pintype "bidirectional"))
      (node (ref "U$6") (pin "10") (pinfunction "10_10") (pintype "passive"))
    )
    (net (code "401") (name "Net-(U$2T-1)") (class "Default")
      (node (ref "U$2") (pin "L2") (pinfunction "1_L2") (pintype "bidirectional"))
      (node (ref "U$7") (pin "10") (pinfunction "10_10") (pintype "passive"))
    )
    (net (code "402") (name "Net-(U$2U-1)") (class "Default")
      (node (ref "U$2") (pin "M1") (pinfunction "1_M1") (pintype "bidirectional"))
      (node (ref "U$6") (pin "11") (pinfunction "11_11") (pintype "passive"))
    )
    (net (code "403") (name "Net-(U$2V-1)") (class "Default")
      (node (ref "U$2") (pin "M2") (pinfunction "1_M2") (pintype "bidirectional"))
      (node (ref "U$7") (pin "11") (pinfunction "11_11") (pintype "passive"))
    )
    (net (code "404") (name "Net-(U$2W-1)") (class "Default")
      (node (ref "U$2") (pin "N1") (pinfunction "1_N1") (pintype "bidirectional"))
      (node (ref "U$6") (pin "12") (pinfunction "12_12") (pintype "passive"))
    )
    (net (code "405") (name "Net-(U$2X-1)") (class "Default")
      (node (ref "U$2") (pin "N2") (pinfunction "1_N2") (pintype "bidirectional"))
      (node (ref "U$7") (pin "12") (pinfunction "12_12") (pintype "passive"))
    )
    (net (code "406") (name "Net-(U$2Y-1)") (class "Default")
      (node (ref "U$2") (pin "P1") (pinfunction "1_P1") (pintype "bidirectional"))
      (node (ref "U$6") (pin "13") (pinfunction "13_13") (pintype "passive"))
    )
    (net (code "407") (name "Net-(U$2Z-1)") (class "Default")
      (node (ref "U$2") (pin "P2") (pinfunction "1_P2") (pintype "bidirectional"))
      (node (ref "U$7") (pin "13") (pinfunction "13_13") (pintype "passive"))
    )
    (net (code "408") (name "VCC") (class "Default")
      (node (ref "C1") (pin "1") (pinfunction "1_1") (pintype "passive"))
      (node (ref "C10") (pin "1") (pinfunction "1_1") (pintype "passive"))
      (node (ref "C11") (pin "1") (pinfunction "1_1") (pintype "passive"))
      (node (ref "C12") (pin "1") (pinfunction "1_1") (pintype "passive"))
      (node (ref "C13") (pin "1") (pinfunction "1_1") (pintype "passive"))
      (node (ref "C14") (pin "1") (pinfunction "1_1") (pintype "passive"))
      (node (ref "C15") (pin "1") (pinfunction "1_1") (pintype "passive"))
      (node (ref "C16") (pin "1") (pinfunction "1_1") (pintype "passive"))
      (node (ref "C17") (pin "1") (pinfunction "1_1") (pintype "passive"))
      (node (ref "C18") (pin "1") (pinfunction "1_1") (pintype "passive"))
      (node (ref "C19") (pin "1") (pinfunction "1_1") (pintype "passive"))
      (node (ref "C2") (pin "1") (pinfunction "1_1") (pintype "passive"))
      (node (ref "C20") (pin "1") (pinfunction "1_1") (pintype "passive"))
      (node (ref "C21") (pin "1") (pinfunction "1_1") (pintype "passive"))
      (node (ref "C22") (pin "1") (pinfunction "1_1") (pintype "passive"))
      (node (ref "C23") (pin "1") (pinfunction "1_1") (pintype "passive"))
      (node (ref "C24") (pin "1") (pinfunction "1_1") (pintype "passive"))
      (node (ref "C3") (pin "1") (pinfunction "1_1") (pintype "passive"))
      (node (ref "C4") (pin "1") (pinfunction "1_1") (pintype "passive"))
      (node (ref "C5") (pin "1") (pinfunction "1_1") (pintype "passive"))
      (node (ref "C6") (pin "1") (pinfunction "1_1") (pintype "passive"))
      (node (ref "C7") (pin "1") (pinfunction "1_1") (pintype "passive"))
      (node (ref "C8") (pin "1") (pinfunction "1_1") (pintype "passive"))
      (node (ref "C9") (pin "1") (pinfunction "1_1") (pintype "passive"))
      (node (ref "IC1") (pin "16") (pinfunction "16_16") (pintype "passive"))
      (node (ref "IC10") (pin "16") (pinfunction "16_16") (pintype "passive"))
      (node (ref "IC11") (pin "16") (pinfunction "16_16") (pintype "passive"))
      (node (ref "IC12") (pin "16") (pinfunction "16_16") (pintype "passive"))
      (node (ref "IC13") (pin "16") (pinfunction "16_16") (pintype "passive"))
      (node (ref "IC14") (pin "16") (pinfunction "16_16") (pintype "passive"))
      (node (ref "IC15") (pin "16") (pinfunction "16_16") (pintype "passive"))
      (node (ref "IC16") (pin "16") (pinfunction "16_16") (pintype "passive"))
      (node (ref "IC17") (pin "16") (pinfunction "16_16") (pintype "passive"))
      (node (ref "IC18") (pin "16") (pinfunction "16_16") (pintype "passive"))
      (node (ref "IC19") (pin "16") (pinfunction "16_16") (pintype "passive"))
      (node (ref "IC2") (pin "16") (pinfunction "16_16") (pintype "passive"))
      (node (ref "IC20") (pin "16") (pinfunction "16_16") (pintype "passive"))
      (node (ref "IC21") (pin "16") (pinfunction "16_16") (pintype "passive"))
      (node (ref "IC22") (pin "16") (pinfunction "16_16") (pintype "passive"))
      (node (ref "IC23") (pin "16") (pinfunction "16_16") (pintype "passive"))
      (node (ref "IC24") (pin "16") (pinfunction "16_16") (pintype "passive"))
      (node (ref "IC3") (pin "16") (pinfunction "16_16") (pintype "passive"))
      (node (ref "IC4") (pin "16") (pinfunction "16_16") (pintype "passive"))
      (node (ref "IC5") (pin "16") (pinfunction "16_16") (pintype "passive"))
      (node (ref "IC6") (pin "16") (pinfunction "16_16") (pintype "passive"))
      (node (ref "IC7") (pin "16") (pinfunction "16_16") (pintype "passive"))
      (node (ref "IC8") (pin "16") (pinfunction "16_16") (pintype "passive"))
      (node (ref "IC9") (pin "16") (pinfunction "16_16") (pintype "passive"))
      (node (ref "SV13") (pin "1") (pinfunction "1_1") (pintype "passive"))
      (node (ref "SV14") (pin "1") (pinfunction "1_1") (pintype "passive"))
      (node (ref "SV15") (pin "1") (pinfunction "1_1") (pintype "passive"))
      (node (ref "SV16") (pin "1") (pinfunction "1_1") (pintype "passive"))
      (node (ref "SV21") (pin "1") (pinfunction "1_1") (pintype "passive"))
      (node (ref "SV22") (pin "1") (pinfunction "1_1") (pintype "passive"))
      (node (ref "SV23") (pin "1") (pinfunction "1_1") (pintype "passive"))
      (node (ref "SV24") (pin "1") (pinfunction "1_1") (pintype "passive"))
      (node (ref "SV29") (pin "1") (pinfunction "1_1") (pintype "passive"))
      (node (ref "SV30") (pin "1") (pinfunction "1_1") (pintype "passive"))
      (node (ref "SV31") (pin "1") (pinfunction "1_1") (pintype "passive"))
      (node (ref "SV32") (pin "1") (pinfunction "1_1") (pintype "passive"))
      (node (ref "SV37") (pin "1") (pinfunction "1_1") (pintype "passive"))
      (node (ref "SV38") (pin "1") (pinfunction "1_1") (pintype "passive"))
      (node (ref "SV39") (pin "1") (pinfunction "1_1") (pintype "passive"))
      (node (ref "SV40") (pin "1") (pinfunction "1_1") (pintype "passive"))
      (node (ref "SV45") (pin "1") (pinfunction "1_1") (pintype "passive"))
      (node (ref "SV46") (pin "1") (pinfunction "1_1") (pintype "passive"))
      (node (ref "SV47") (pin "1") (pinfunction "1_1") (pintype "passive"))
      (node (ref "SV48") (pin "1") (pinfunction "1_1") (pintype "passive"))
      (node (ref "SV5") (pin "1") (pinfunction "1_1") (pintype "passive"))
      (node (ref "SV6") (pin "1") (pinfunction "1_1") (pintype "passive"))
      (node (ref "SV7") (pin "1") (pinfunction "1_1") (pintype "passive"))
      (node (ref "SV8") (pin "1") (pinfunction "1_1") (pintype "passive"))
      (node (ref "U$4") (pin "A2") (pinfunction "1_A2") (pintype "bidirectional"))
      (node (ref "U$5") (pin "1") (pinfunction "1_1") (pintype "passive"))
    )
  )
)
